# OhBaby10-1.net
KiCad netlist of a schematic drawn in EAGLE
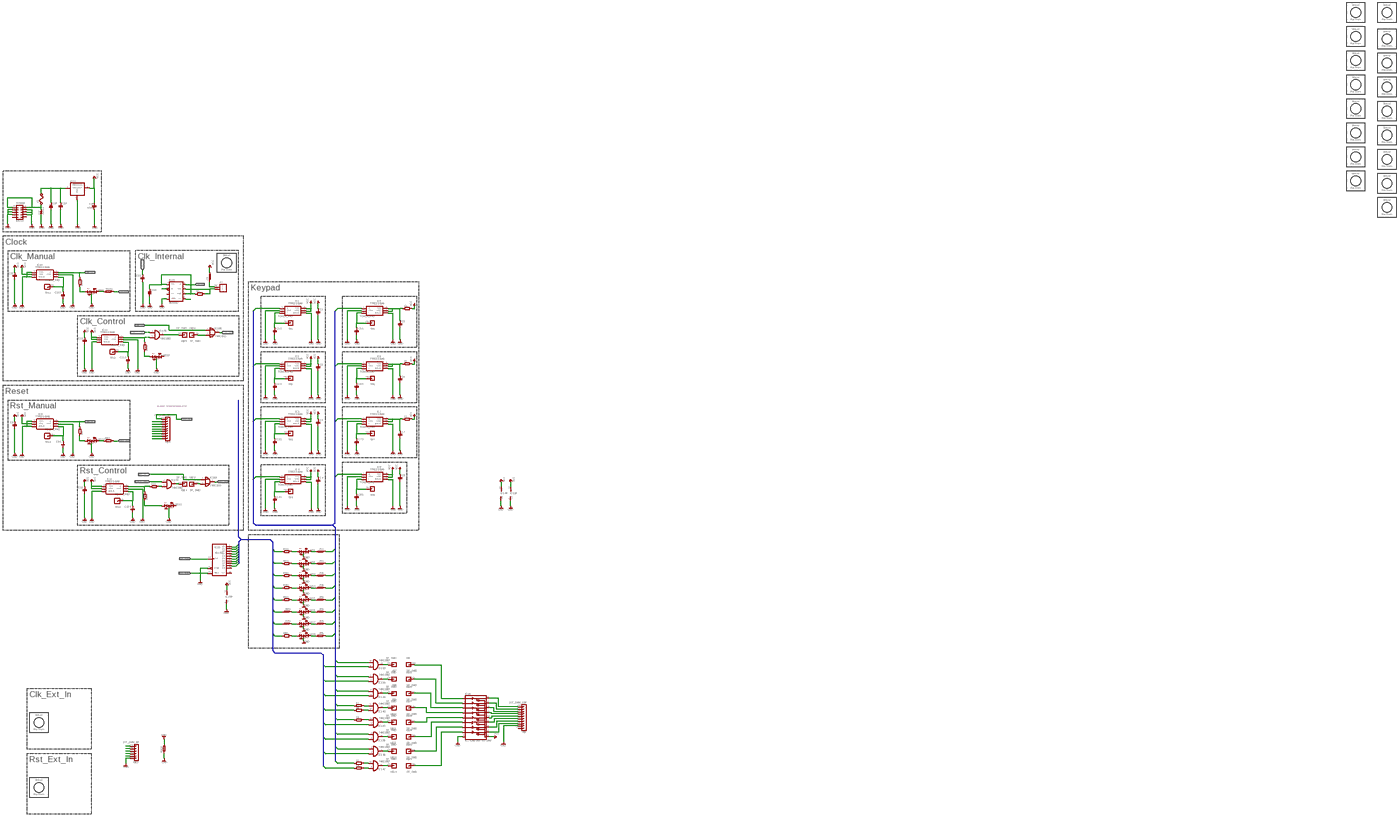
[diagram p0: schematic, sheet 1, overview]
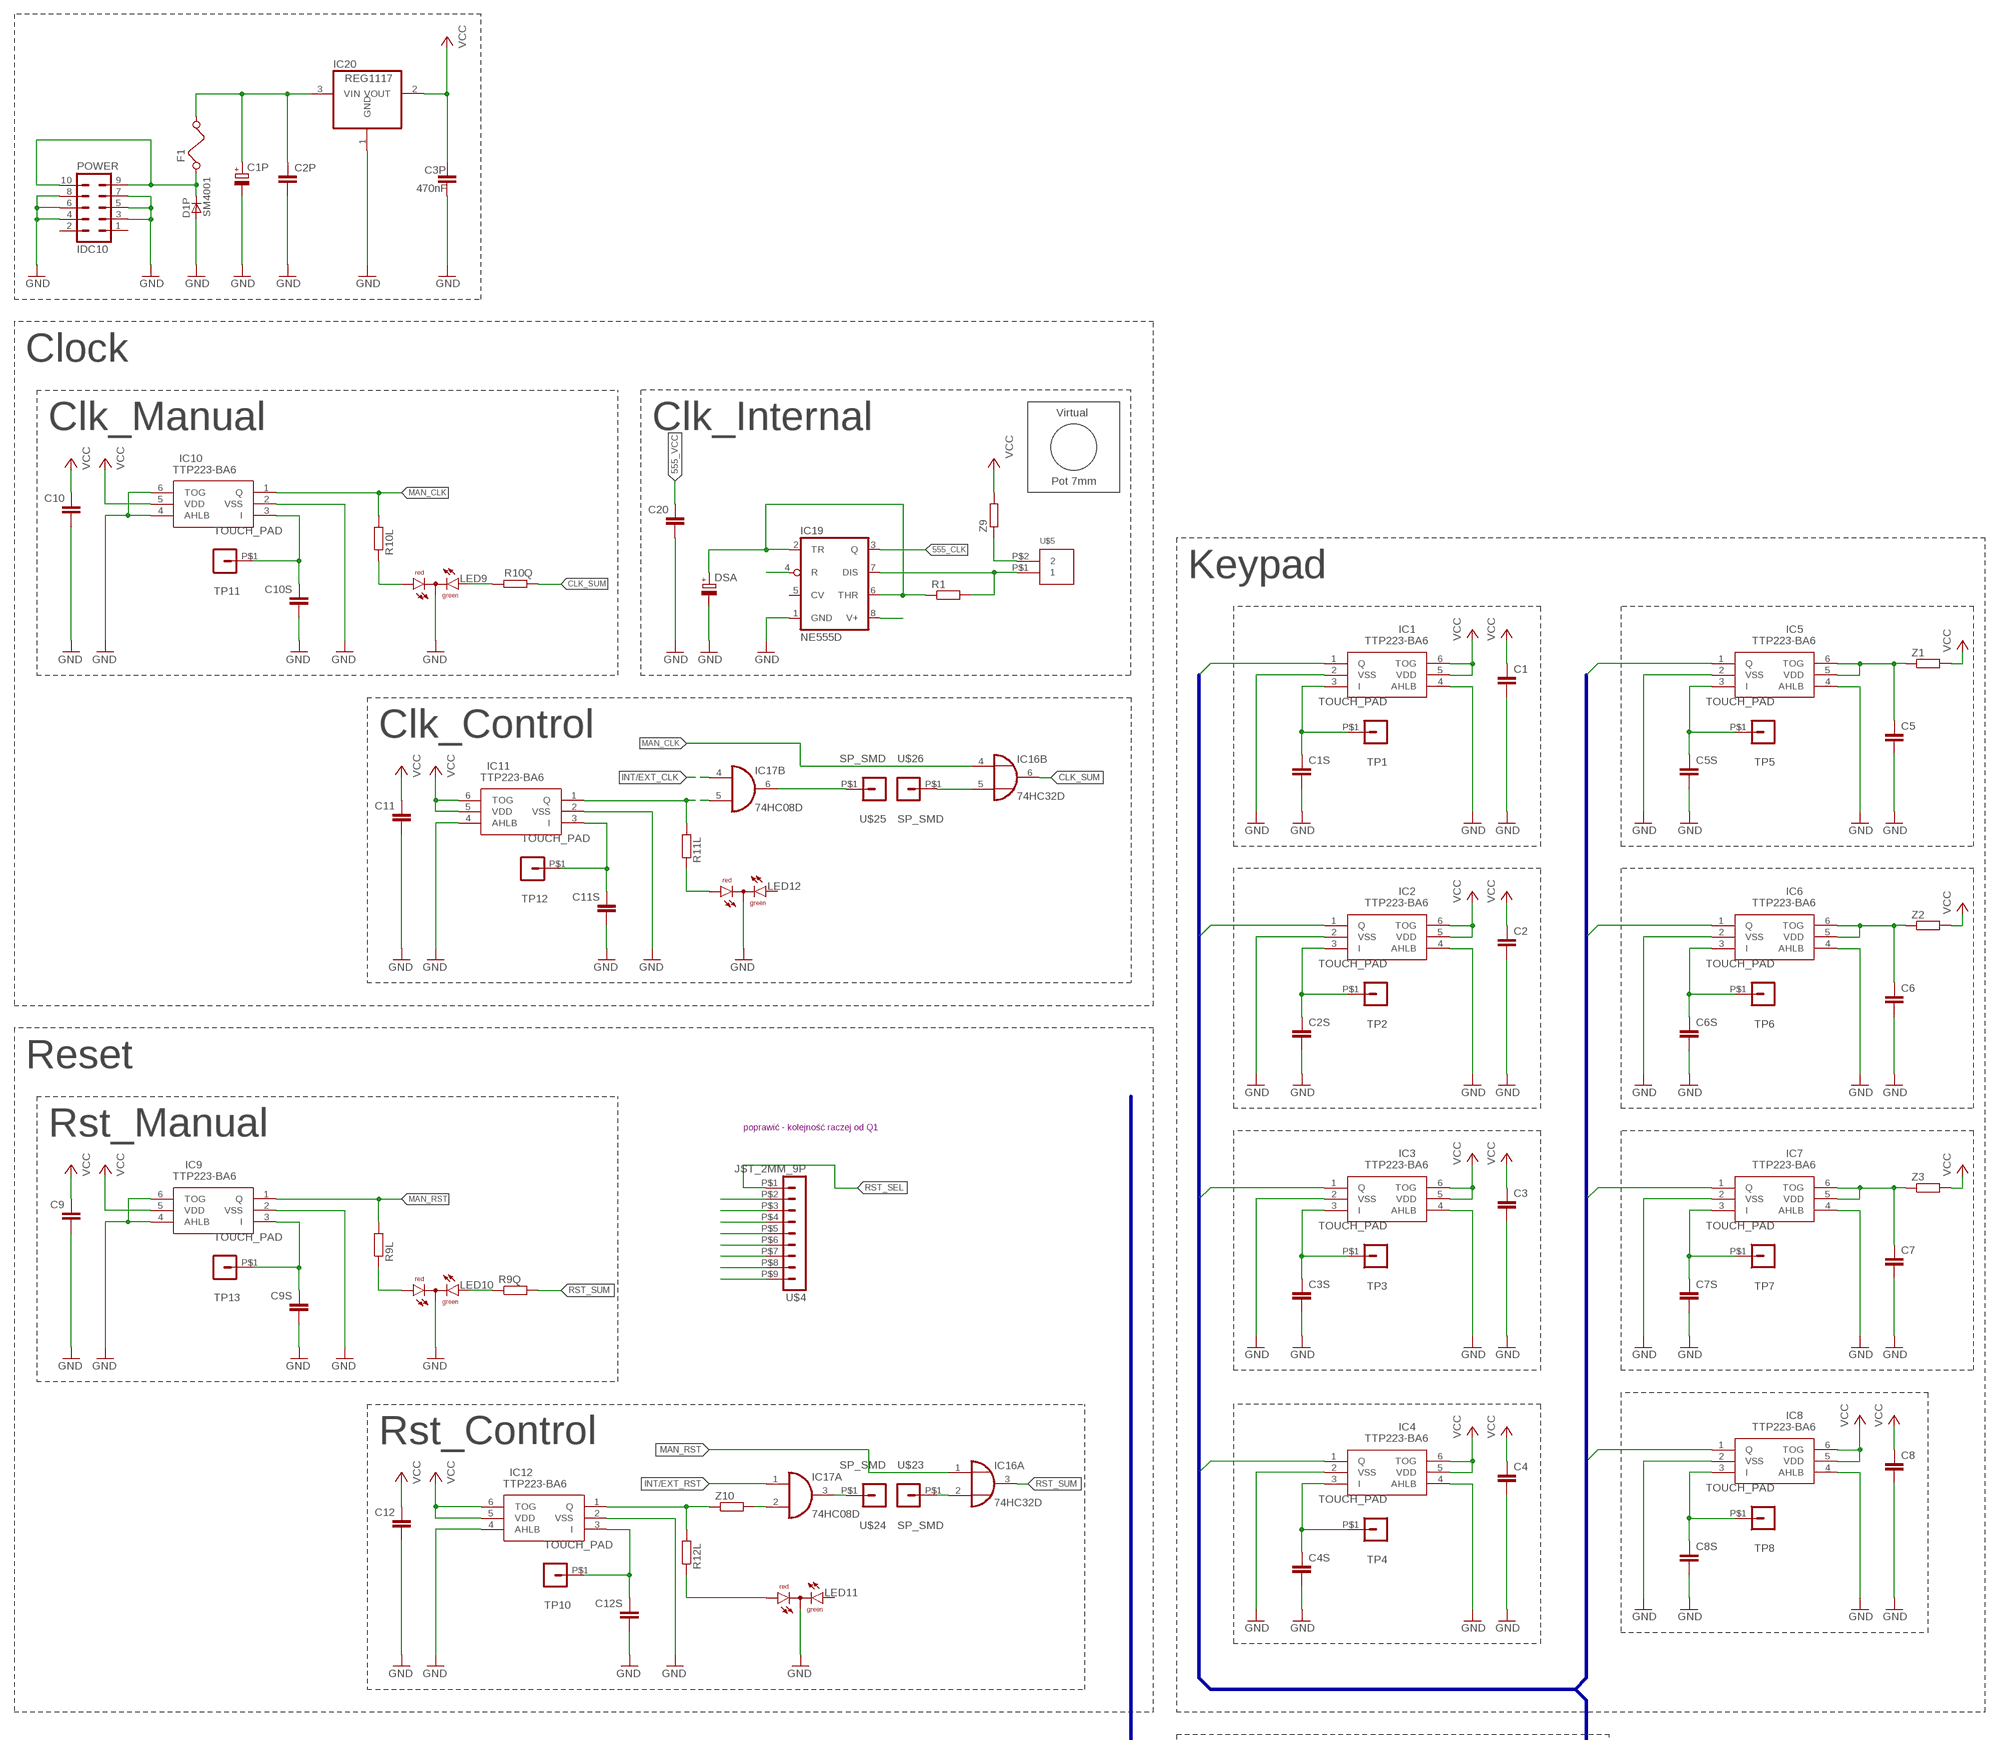
[diagram p1: schematic, sheet 1, part 1 of 5]
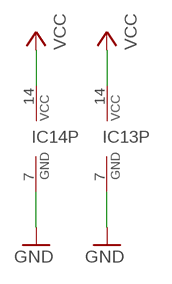
[diagram p2: schematic, sheet 1, part 2 of 5]
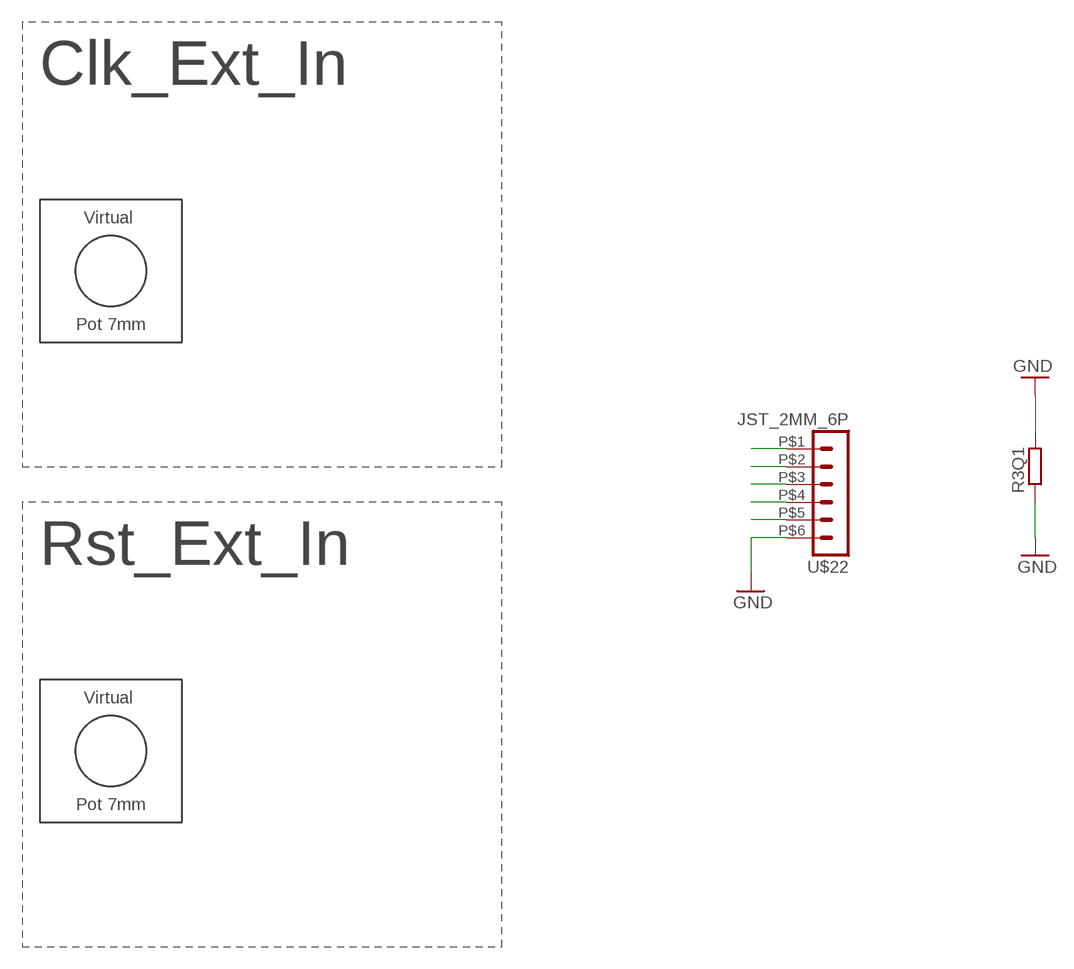
[diagram p3: schematic, sheet 1, part 3 of 5]
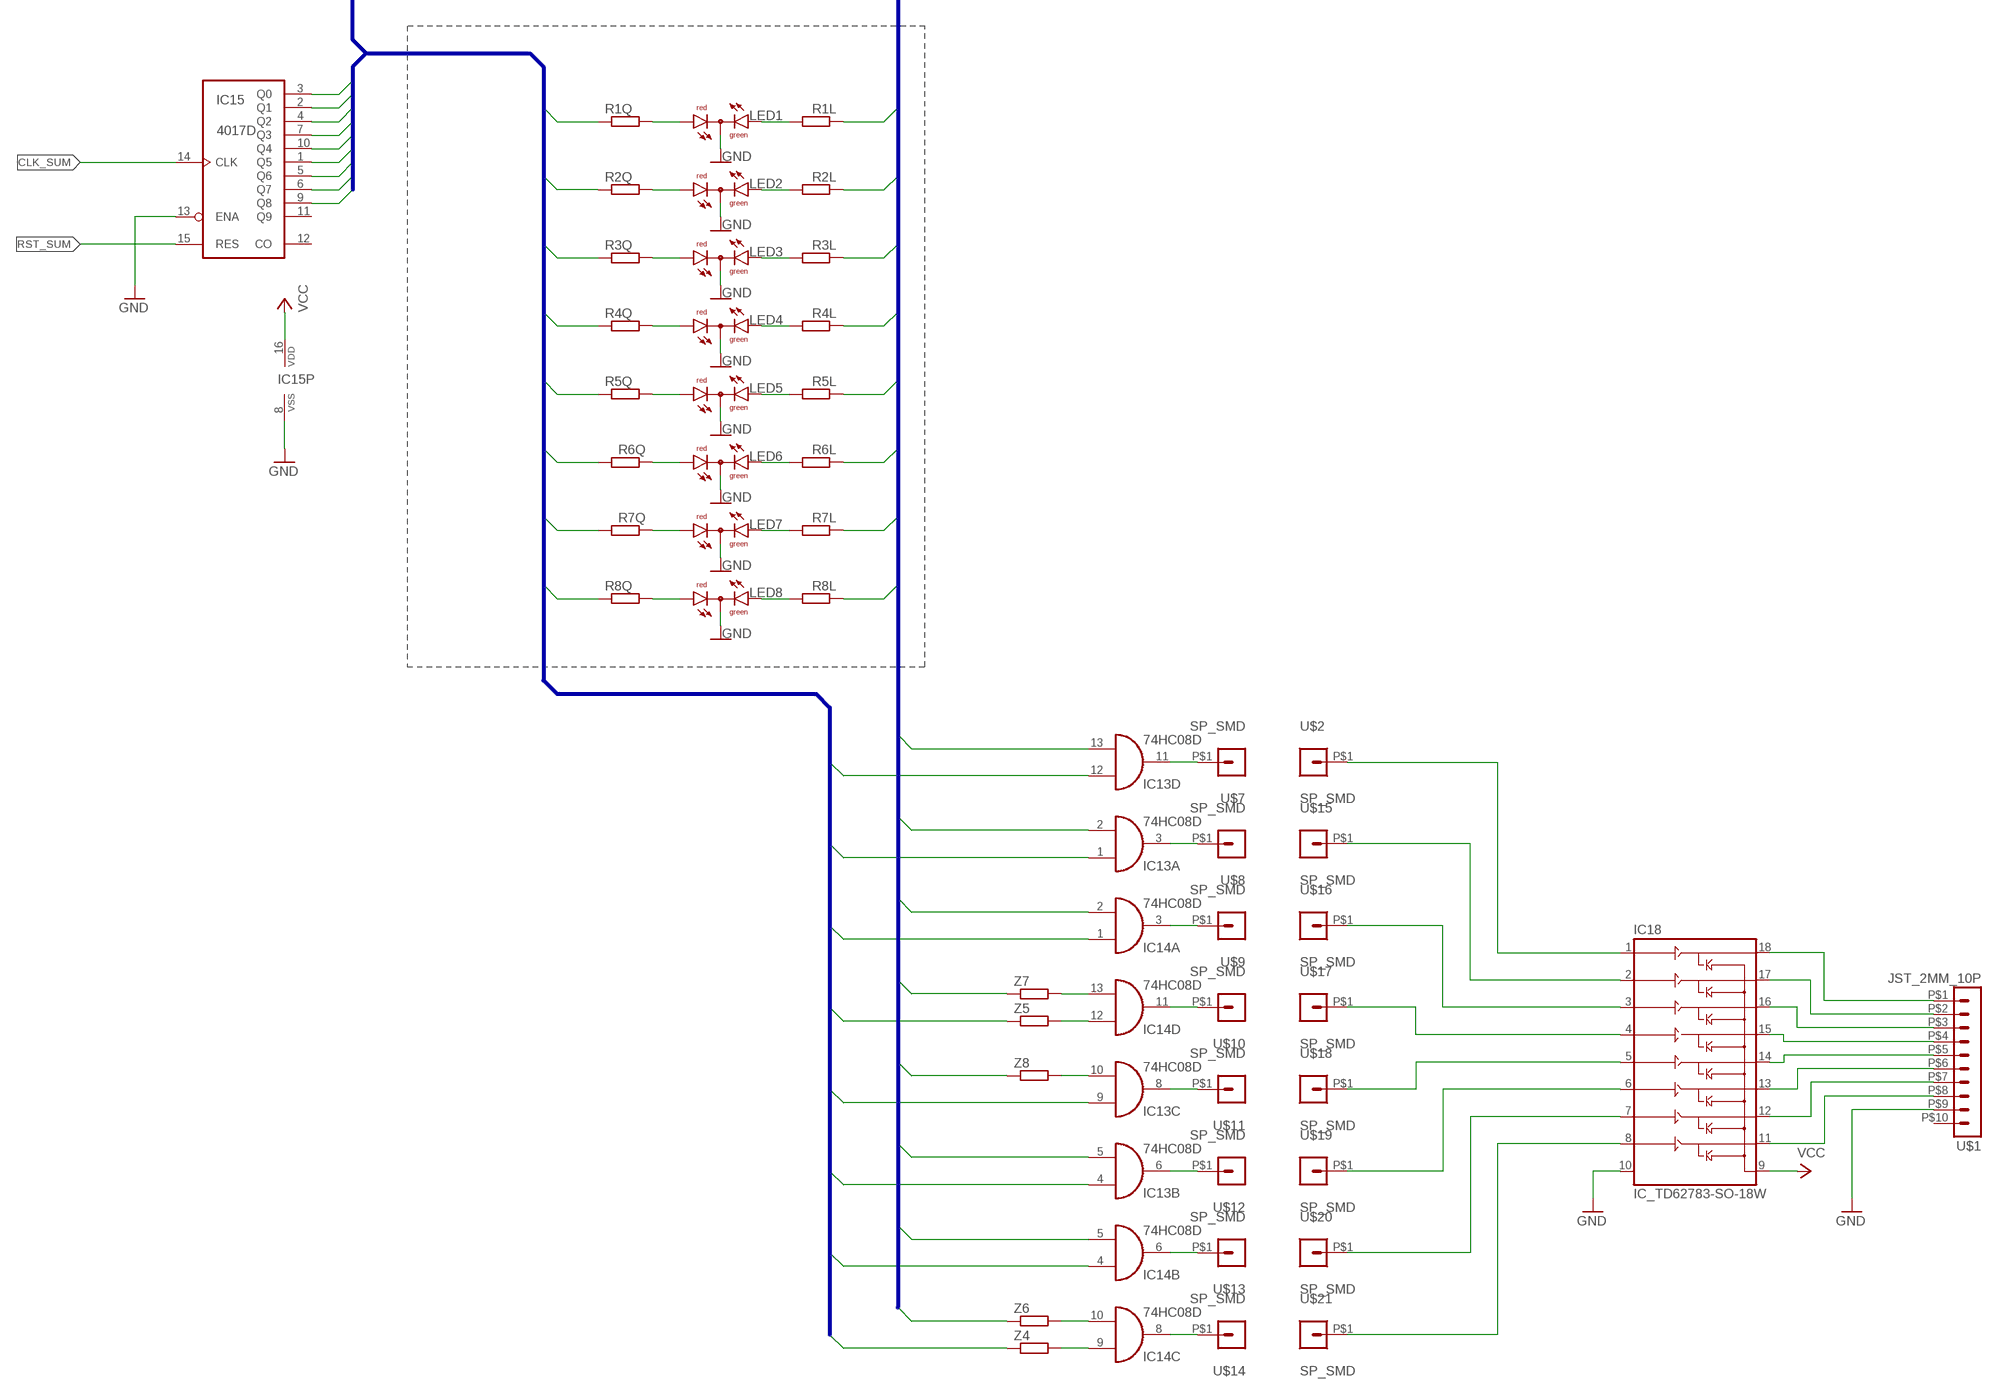
[diagram p4: schematic, sheet 1, part 4 of 5]
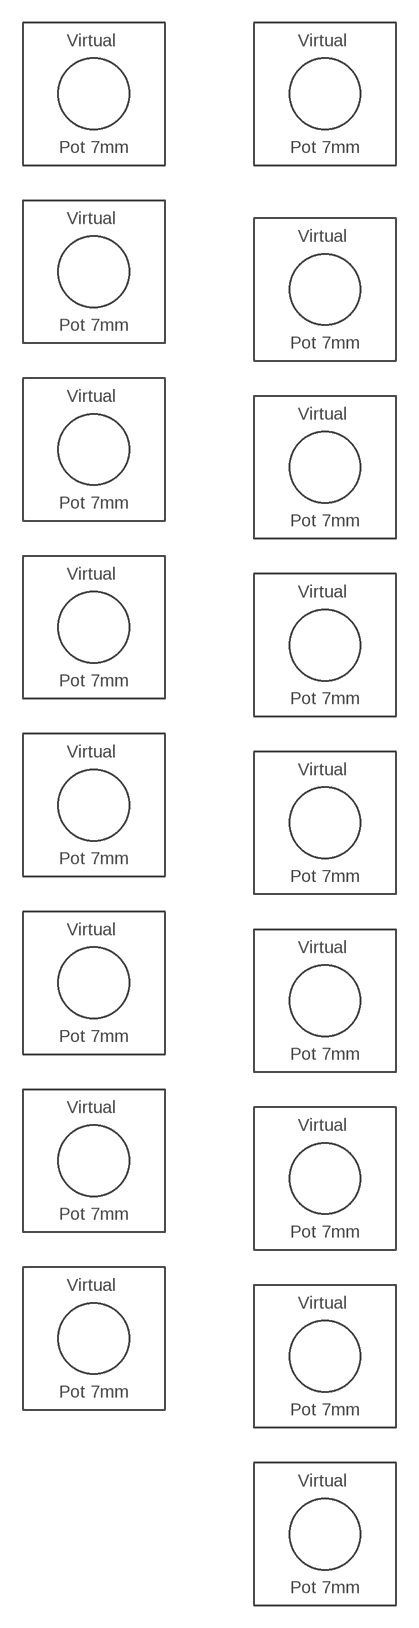
[diagram p5: schematic, sheet 1, part 5 of 5]

(export (version "E")
  (design (tool "Eeschema 10.0.6"))
  (components
    (comp (ref "C1")
      (value "C-EUC0805")
      (footprint "eagle-import:C0805")
      (libsource (lib "eagle-import") (part "rcl_334_C-EUC0805"))
    )
    (comp (ref "C1P")
      (value "CPOL-EU153CLV-0405")
      (footprint "eagle-import:153CLV-0405")
      (libsource (lib "eagle-import") (part "CPOL-EU153CLV-0405"))
    )
    (comp (ref "C1S")
      (value "C-EUC0805")
      (footprint "eagle-import:C0805")
      (libsource (lib "eagle-import") (part "rcl_334_C-EUC0805"))
    )
    (comp (ref "C2")
      (value "C-EUC0805")
      (footprint "eagle-import:C0805")
      (libsource (lib "eagle-import") (part "rcl_334_C-EUC0805"))
    )
    (comp (ref "C2P")
      (value "C-EUC0805K")
      (footprint "eagle-import:C0805K")
      (libsource (lib "eagle-import") (part "rcl_334_C-EUC0805K"))
    )
    (comp (ref "C2S")
      (value "C-EUC0805")
      (footprint "eagle-import:C0805")
      (libsource (lib "eagle-import") (part "rcl_334_C-EUC0805"))
    )
    (comp (ref "C3")
      (value "C-EUC0805")
      (footprint "eagle-import:C0805")
      (libsource (lib "eagle-import") (part "rcl_334_C-EUC0805"))
    )
    (comp (ref "C3P")
      (value "470nF")
      (footprint "eagle-import:C0805")
      (fields (field (name "SPICEPREFIX") "C"))
      (libsource (lib "eagle-import") (part "C-EUC0805"))
    )
    (comp (ref "C3S")
      (value "C-EUC0805")
      (footprint "eagle-import:C0805")
      (libsource (lib "eagle-import") (part "rcl_334_C-EUC0805"))
    )
    (comp (ref "C4")
      (value "C-EUC0805")
      (footprint "eagle-import:C0805")
      (libsource (lib "eagle-import") (part "rcl_334_C-EUC0805"))
    )
    (comp (ref "C4S")
      (value "C-EUC0805")
      (footprint "eagle-import:C0805")
      (libsource (lib "eagle-import") (part "rcl_334_C-EUC0805"))
    )
    (comp (ref "C5")
      (value "C-EUC0805")
      (footprint "eagle-import:C0805")
      (libsource (lib "eagle-import") (part "rcl_334_C-EUC0805"))
    )
    (comp (ref "C5S")
      (value "C-EUC0805")
      (footprint "eagle-import:C0805")
      (libsource (lib "eagle-import") (part "rcl_334_C-EUC0805"))
    )
    (comp (ref "C6")
      (value "C-EUC0805")
      (footprint "eagle-import:C0805")
      (libsource (lib "eagle-import") (part "rcl_334_C-EUC0805"))
    )
    (comp (ref "C6S")
      (value "C-EUC0805")
      (footprint "eagle-import:C0805")
      (libsource (lib "eagle-import") (part "rcl_334_C-EUC0805"))
    )
    (comp (ref "C7")
      (value "C-EUC0805")
      (footprint "eagle-import:C0805")
      (libsource (lib "eagle-import") (part "rcl_334_C-EUC0805"))
    )
    (comp (ref "C7S")
      (value "C-EUC0805")
      (footprint "eagle-import:C0805")
      (libsource (lib "eagle-import") (part "rcl_334_C-EUC0805"))
    )
    (comp (ref "C8")
      (value "C-EUC0805")
      (footprint "eagle-import:C0805")
      (libsource (lib "eagle-import") (part "rcl_334_C-EUC0805"))
    )
    (comp (ref "C8S")
      (value "C-EUC0805")
      (footprint "eagle-import:C0805")
      (libsource (lib "eagle-import") (part "rcl_334_C-EUC0805"))
    )
    (comp (ref "C9")
      (value "C-EUC0805")
      (footprint "eagle-import:C0805")
      (libsource (lib "eagle-import") (part "rcl_334_C-EUC0805"))
    )
    (comp (ref "C9S")
      (value "C-EUC0805")
      (footprint "eagle-import:C0805")
      (libsource (lib "eagle-import") (part "rcl_334_C-EUC0805"))
    )
    (comp (ref "C10")
      (value "C-EUC0805")
      (footprint "eagle-import:C0805")
      (libsource (lib "eagle-import") (part "rcl_334_C-EUC0805"))
    )
    (comp (ref "C10S")
      (value "C-EUC0805")
      (footprint "eagle-import:C0805")
      (libsource (lib "eagle-import") (part "rcl_334_C-EUC0805"))
    )
    (comp (ref "C11")
      (value "C-EUC0805")
      (footprint "eagle-import:C0805")
      (libsource (lib "eagle-import") (part "rcl_334_C-EUC0805"))
    )
    (comp (ref "C11S")
      (value "C-EUC0805")
      (footprint "eagle-import:C0805")
      (libsource (lib "eagle-import") (part "rcl_334_C-EUC0805"))
    )
    (comp (ref "C12")
      (value "C-EUC0805")
      (footprint "eagle-import:C0805")
      (libsource (lib "eagle-import") (part "rcl_334_C-EUC0805"))
    )
    (comp (ref "C12S")
      (value "C-EUC0805")
      (footprint "eagle-import:C0805")
      (libsource (lib "eagle-import") (part "rcl_334_C-EUC0805"))
    )
    (comp (ref "C20")
      (value "C-EUC0805")
      (footprint "eagle-import:C0805")
      (libsource (lib "eagle-import") (part "rcl_334_C-EUC0805"))
    )
    (comp (ref "CV_OUT")
      (value "JACK3.5")
      (footprint "eagle-import:JACK_FANCY")
      (libsource (lib "eagle-import") (part "JACK3.5"))
    )
    (comp (ref "D1P")
      (value "SM4001")
      (footprint "eagle-import:MELF-MLL41_DO213AB")
      (libsource (lib "eagle-import") (part "SM4001"))
    )
    (comp (ref "DSA")
      (value "CPOL-EU153CLV-0405")
      (footprint "eagle-import:153CLV-0405")
      (libsource (lib "eagle-import") (part "CPOL-EU153CLV-0405"))
    )
    (comp (ref "EXT_CLK_IN")
      (value "JACK3.5")
      (footprint "eagle-import:JACK_FANCY")
      (libsource (lib "eagle-import") (part "JACK3.5"))
    )
    (comp (ref "EXT_CLK_IN1")
      (value "JACK3.5")
      (footprint "eagle-import:JACK_FANCY")
      (libsource (lib "eagle-import") (part "JACK3.5"))
    )
    (comp (ref "F1")
      (value "FUSEB")
      (footprint "eagle-import:0805")
      (libsource (lib "eagle-import") (part "FUSEB"))
    )
    (comp (ref "IC1")
      (value "TTP223-BA6")
      (footprint "eagle-import:SOT95P285X126-6N")
      (libsource (lib "eagle-import") (part "TTP223-BA6"))
    )
    (comp (ref "IC2")
      (value "TTP223-BA6")
      (footprint "eagle-import:SOT95P285X126-6N")
      (libsource (lib "eagle-import") (part "TTP223-BA6"))
    )
    (comp (ref "IC3")
      (value "TTP223-BA6")
      (footprint "eagle-import:SOT95P285X126-6N")
      (libsource (lib "eagle-import") (part "TTP223-BA6"))
    )
    (comp (ref "IC4")
      (value "TTP223-BA6")
      (footprint "eagle-import:SOT95P285X126-6N")
      (libsource (lib "eagle-import") (part "TTP223-BA6"))
    )
    (comp (ref "IC5")
      (value "TTP223-BA6")
      (footprint "eagle-import:SOT95P285X126-6N")
      (libsource (lib "eagle-import") (part "TTP223-BA6"))
    )
    (comp (ref "IC6")
      (value "TTP223-BA6")
      (footprint "eagle-import:SOT95P285X126-6N")
      (libsource (lib "eagle-import") (part "TTP223-BA6"))
    )
    (comp (ref "IC7")
      (value "TTP223-BA6")
      (footprint "eagle-import:SOT95P285X126-6N")
      (libsource (lib "eagle-import") (part "TTP223-BA6"))
    )
    (comp (ref "IC8")
      (value "TTP223-BA6")
      (footprint "eagle-import:SOT95P285X126-6N")
      (libsource (lib "eagle-import") (part "TTP223-BA6"))
    )
    (comp (ref "IC9")
      (value "TTP223-BA6")
      (footprint "eagle-import:SOT95P285X126-6N")
      (libsource (lib "eagle-import") (part "TTP223-BA6"))
    )
    (comp (ref "IC10")
      (value "TTP223-BA6")
      (footprint "eagle-import:SOT95P285X126-6N")
      (libsource (lib "eagle-import") (part "TTP223-BA6"))
    )
    (comp (ref "IC11")
      (value "TTP223-BA6")
      (footprint "eagle-import:SOT95P285X126-6N")
      (libsource (lib "eagle-import") (part "TTP223-BA6"))
    )
    (comp (ref "IC12")
      (value "TTP223-BA6")
      (footprint "eagle-import:SOT95P285X126-6N")
      (libsource (lib "eagle-import") (part "TTP223-BA6"))
    )
    (comp (ref "IC13")
      (value "74HC08D")
      (footprint "eagle-import:SO14")
      (libsource (lib "eagle-import") (part "7408DHC"))
    )
    (comp (ref "IC14")
      (value "74HC08D")
      (footprint "eagle-import:SO14")
      (libsource (lib "eagle-import") (part "7408DHC"))
    )
    (comp (ref "IC15")
      (value "4017D")
      (footprint "eagle-import:SO16")
      (libsource (lib "eagle-import") (part "4017D"))
    )
    (comp (ref "IC16")
      (value "74HC32D")
      (footprint "eagle-import:SO14")
      (libsource (lib "eagle-import") (part "7432DHC"))
    )
    (comp (ref "IC17")
      (value "74HC08D")
      (footprint "eagle-import:SO14")
      (libsource (lib "eagle-import") (part "7408DHC"))
    )
    (comp (ref "IC18")
      (value "IC_TD62783-SO-18W")
      (footprint "eagle-import:SO-18L")
      (libsource (lib "eagle-import") (part "IC_TD62783-SO-18W"))
    )
    (comp (ref "IC19")
      (value "NE555D")
      (footprint "eagle-import:SO08")
      (libsource (lib "eagle-import") (part "555DNE"))
    )
    (comp (ref "IC20")
      (value "REG1117")
      (footprint "eagle-import:SOT223")
      (libsource (lib "eagle-import") (part "REG1117"))
    )
    (comp (ref "LED1")
      (value "LED_3PIN")
      (footprint "eagle-import:LED_3PIN_SMD")
      (libsource (lib "eagle-import") (part "LED_3PIN"))
    )
    (comp (ref "LED2")
      (value "LED_3PIN")
      (footprint "eagle-import:LED_3PIN_SMD")
      (libsource (lib "eagle-import") (part "LED_3PIN"))
    )
    (comp (ref "LED3")
      (value "LED_3PIN")
      (footprint "eagle-import:LED_3PIN_SMD")
      (libsource (lib "eagle-import") (part "LED_3PIN"))
    )
    (comp (ref "LED4")
      (value "LED_3PIN")
      (footprint "eagle-import:LED_3PIN_SMD")
      (libsource (lib "eagle-import") (part "LED_3PIN"))
    )
    (comp (ref "LED5")
      (value "LED_3PIN")
      (footprint "eagle-import:LED_3PIN_SMD")
      (libsource (lib "eagle-import") (part "LED_3PIN"))
    )
    (comp (ref "LED6")
      (value "LED_3PIN")
      (footprint "eagle-import:LED_3PIN_SMD")
      (libsource (lib "eagle-import") (part "LED_3PIN"))
    )
    (comp (ref "LED7")
      (value "LED_3PIN")
      (footprint "eagle-import:LED_3PIN_SMD")
      (libsource (lib "eagle-import") (part "LED_3PIN"))
    )
    (comp (ref "LED8")
      (value "LED_3PIN")
      (footprint "eagle-import:LED_3PIN_SMD")
      (libsource (lib "eagle-import") (part "LED_3PIN"))
    )
    (comp (ref "LED9")
      (value "LED_3PIN")
      (footprint "eagle-import:LED_3PIN_SMD")
      (libsource (lib "eagle-import") (part "LED_3PIN"))
    )
    (comp (ref "LED10")
      (value "LED_3PIN")
      (footprint "eagle-import:LED_3PIN_SMD")
      (libsource (lib "eagle-import") (part "LED_3PIN"))
    )
    (comp (ref "LED11")
      (value "LED_3PIN")
      (footprint "eagle-import:LED_3PIN_SMD")
      (libsource (lib "eagle-import") (part "LED_3PIN"))
    )
    (comp (ref "LED12")
      (value "LED_3PIN")
      (footprint "eagle-import:LED_3PIN_SMD")
      (libsource (lib "eagle-import") (part "LED_3PIN"))
    )
    (comp (ref "OUT_S1")
      (value "JACK3.5")
      (footprint "eagle-import:JACK_FANCY")
      (libsource (lib "eagle-import") (part "JACK3.5"))
    )
    (comp (ref "OUT_S2")
      (value "JACK3.5")
      (footprint "eagle-import:JACK_FANCY")
      (libsource (lib "eagle-import") (part "JACK3.5"))
    )
    (comp (ref "OUT_S3")
      (value "JACK3.5")
      (footprint "eagle-import:JACK_FANCY")
      (libsource (lib "eagle-import") (part "JACK3.5"))
    )
    (comp (ref "OUT_S4")
      (value "JACK3.5")
      (footprint "eagle-import:JACK_FANCY")
      (libsource (lib "eagle-import") (part "JACK3.5"))
    )
    (comp (ref "OUT_S5")
      (value "JACK3.5")
      (footprint "eagle-import:JACK_FANCY")
      (libsource (lib "eagle-import") (part "JACK3.5"))
    )
    (comp (ref "OUT_S6")
      (value "JACK3.5")
      (footprint "eagle-import:JACK_FANCY")
      (libsource (lib "eagle-import") (part "JACK3.5"))
    )
    (comp (ref "OUT_S7")
      (value "JACK3.5")
      (footprint "eagle-import:JACK_FANCY")
      (libsource (lib "eagle-import") (part "JACK3.5"))
    )
    (comp (ref "OUT_S8")
      (value "JACK3.5")
      (footprint "eagle-import:JACK_FANCY")
      (libsource (lib "eagle-import") (part "JACK3.5"))
    )
    (comp (ref "POT_S1")
      (value "V_POT")
      (footprint "eagle-import:POT_FANCY")
      (libsource (lib "eagle-import") (part "V_POT"))
    )
    (comp (ref "POT_S2")
      (value "V_POT")
      (footprint "eagle-import:POT_FANCY")
      (libsource (lib "eagle-import") (part "V_POT"))
    )
    (comp (ref "POT_S3")
      (value "V_POT")
      (footprint "eagle-import:POT_FANCY")
      (libsource (lib "eagle-import") (part "V_POT"))
    )
    (comp (ref "POT_S4")
      (value "V_POT")
      (footprint "eagle-import:POT_FANCY")
      (libsource (lib "eagle-import") (part "V_POT"))
    )
    (comp (ref "POT_S5")
      (value "V_POT")
      (footprint "eagle-import:POT_FANCY")
      (libsource (lib "eagle-import") (part "V_POT"))
    )
    (comp (ref "POT_S6")
      (value "V_POT")
      (footprint "eagle-import:POT_FANCY")
      (libsource (lib "eagle-import") (part "V_POT"))
    )
    (comp (ref "POT_S7")
      (value "V_POT")
      (footprint "eagle-import:POT_FANCY")
      (libsource (lib "eagle-import") (part "V_POT"))
    )
    (comp (ref "POT_S8")
      (value "V_POT")
      (footprint "eagle-import:POT_FANCY")
      (libsource (lib "eagle-import") (part "V_POT"))
    )
    (comp (ref "POWER")
      (value "IDC10")
      (footprint "eagle-import:ML10")
      (libsource (lib "eagle-import") (part "IDC10"))
    )
    (comp (ref "R1")
      (value "R-EU_R1206")
      (footprint "eagle-import:R1206")
      (libsource (lib "eagle-import") (part "R-EU_R1206"))
    )
    (comp (ref "R1L")
      (value "R-EU_R0805")
      (footprint "eagle-import:R0805")
      (libsource (lib "eagle-import") (part "R-EU_R0805"))
    )
    (comp (ref "R1Q")
      (value "R-EU_R1206")
      (footprint "eagle-import:R1206")
      (libsource (lib "eagle-import") (part "R-EU_R1206"))
    )
    (comp (ref "R2L")
      (value "R-EU_R0805")
      (footprint "eagle-import:R0805")
      (libsource (lib "eagle-import") (part "R-EU_R0805"))
    )
    (comp (ref "R2Q")
      (value "R-EU_R1206")
      (footprint "eagle-import:R1206")
      (libsource (lib "eagle-import") (part "R-EU_R1206"))
    )
    (comp (ref "R3L")
      (value "R-EU_R0805")
      (footprint "eagle-import:R0805")
      (libsource (lib "eagle-import") (part "R-EU_R0805"))
    )
    (comp (ref "R3Q")
      (value "R-EU_R1206")
      (footprint "eagle-import:R1206")
      (libsource (lib "eagle-import") (part "R-EU_R1206"))
    )
    (comp (ref "R3Q1")
      (value "R-EU_R1206")
      (footprint "eagle-import:R1206")
      (libsource (lib "eagle-import") (part "R-EU_R1206"))
    )
    (comp (ref "R4L")
      (value "R-EU_R0805")
      (footprint "eagle-import:R0805")
      (libsource (lib "eagle-import") (part "R-EU_R0805"))
    )
    (comp (ref "R4Q")
      (value "R-EU_R1206")
      (footprint "eagle-import:R1206")
      (libsource (lib "eagle-import") (part "R-EU_R1206"))
    )
    (comp (ref "R5L")
      (value "R-EU_R0805")
      (footprint "eagle-import:R0805")
      (libsource (lib "eagle-import") (part "R-EU_R0805"))
    )
    (comp (ref "R5Q")
      (value "R-EU_R1206")
      (footprint "eagle-import:R1206")
      (libsource (lib "eagle-import") (part "R-EU_R1206"))
    )
    (comp (ref "R6L")
      (value "R-EU_R0805")
      (footprint "eagle-import:R0805")
      (libsource (lib "eagle-import") (part "R-EU_R0805"))
    )
    (comp (ref "R6Q")
      (value "R-EU_R0805")
      (footprint "eagle-import:R0805")
      (libsource (lib "eagle-import") (part "R-EU_R0805"))
    )
    (comp (ref "R7L")
      (value "R-EU_R0805")
      (footprint "eagle-import:R0805")
      (libsource (lib "eagle-import") (part "R-EU_R0805"))
    )
    (comp (ref "R7Q")
      (value "R-EU_R0805")
      (footprint "eagle-import:R0805")
      (libsource (lib "eagle-import") (part "R-EU_R0805"))
    )
    (comp (ref "R8L")
      (value "R-EU_R0805")
      (footprint "eagle-import:R0805")
      (libsource (lib "eagle-import") (part "R-EU_R0805"))
    )
    (comp (ref "R8Q")
      (value "R-EU_R1206")
      (footprint "eagle-import:R1206")
      (libsource (lib "eagle-import") (part "R-EU_R1206"))
    )
    (comp (ref "R9L")
      (value "R-EU_R0805")
      (footprint "eagle-import:R0805")
      (libsource (lib "eagle-import") (part "R-EU_R0805"))
    )
    (comp (ref "R9Q")
      (value "R-EU_R1206")
      (footprint "eagle-import:R1206")
      (libsource (lib "eagle-import") (part "R-EU_R1206"))
    )
    (comp (ref "R10L")
      (value "R-EU_R0805")
      (footprint "eagle-import:R0805")
      (libsource (lib "eagle-import") (part "R-EU_R0805"))
    )
    (comp (ref "R10Q")
      (value "R-EU_R0805")
      (footprint "eagle-import:R0805")
      (libsource (lib "eagle-import") (part "R-EU_R0805"))
    )
    (comp (ref "R11L")
      (value "R-EU_R0805")
      (footprint "eagle-import:R0805")
      (libsource (lib "eagle-import") (part "R-EU_R0805"))
    )
    (comp (ref "R12L")
      (value "R-EU_R0805")
      (footprint "eagle-import:R0805")
      (libsource (lib "eagle-import") (part "R-EU_R0805"))
    )
    (comp (ref "TP1")
      (value "TOUCH_PAD")
      (footprint "eagle-import:TOUCH_PAD_8X8")
      (libsource (lib "eagle-import") (part "TOUCH_PAD"))
    )
    (comp (ref "TP2")
      (value "TOUCH_PAD")
      (footprint "eagle-import:TOUCH_PAD_8X8")
      (libsource (lib "eagle-import") (part "TOUCH_PAD"))
    )
    (comp (ref "TP3")
      (value "TOUCH_PAD")
      (footprint "eagle-import:TOUCH_PAD_8X8")
      (libsource (lib "eagle-import") (part "TOUCH_PAD"))
    )
    (comp (ref "TP4")
      (value "TOUCH_PAD")
      (footprint "eagle-import:TOUCH_PAD_8X8")
      (libsource (lib "eagle-import") (part "TOUCH_PAD"))
    )
    (comp (ref "TP5")
      (value "TOUCH_PAD")
      (footprint "eagle-import:TOUCH_PAD_8X8")
      (libsource (lib "eagle-import") (part "TOUCH_PAD"))
    )
    (comp (ref "TP6")
      (value "TOUCH_PAD")
      (footprint "eagle-import:TOUCH_PAD_8X8")
      (libsource (lib "eagle-import") (part "TOUCH_PAD"))
    )
    (comp (ref "TP7")
      (value "TOUCH_PAD")
      (footprint "eagle-import:TOUCH_PAD_8X8")
      (libsource (lib "eagle-import") (part "TOUCH_PAD"))
    )
    (comp (ref "TP8")
      (value "TOUCH_PAD")
      (footprint "eagle-import:TOUCH_PAD_8X8")
      (libsource (lib "eagle-import") (part "TOUCH_PAD"))
    )
    (comp (ref "TP10")
      (value "TOUCH_PAD")
      (footprint "eagle-import:TOUCH_PAD_8X8")
      (libsource (lib "eagle-import") (part "TOUCH_PAD"))
    )
    (comp (ref "TP11")
      (value "TOUCH_PAD")
      (footprint "eagle-import:TOUCH_PAD_8X8")
      (libsource (lib "eagle-import") (part "TOUCH_PAD"))
    )
    (comp (ref "TP12")
      (value "TOUCH_PAD")
      (footprint "eagle-import:TOUCH_PAD_8X8")
      (libsource (lib "eagle-import") (part "TOUCH_PAD"))
    )
    (comp (ref "TP13")
      (value "TOUCH_PAD")
      (footprint "eagle-import:TOUCH_PAD_8X8")
      (libsource (lib "eagle-import") (part "TOUCH_PAD"))
    )
    (comp (ref "U$1")
      (value "JST_2MM_10P")
      (footprint "eagle-import:JST_2MM_10P")
      (libsource (lib "eagle-import") (part "JST_2MM_10P"))
    )
    (comp (ref "U$2")
      (value "SP_SMD")
      (footprint "eagle-import:SINGLE_PAD_SMD")
      (libsource (lib "eagle-import") (part "SP_SMD"))
    )
    (comp (ref "U$4")
      (value "JST_2MM_9P")
      (footprint "eagle-import:JST_2MM_9P")
      (libsource (lib "eagle-import") (part "JST_2MM_9P"))
    )
    (comp (ref "U$5")
      (value "JST_2MM_2P")
      (footprint "eagle-import:JST_2MM_2P")
      (libsource (lib "eagle-import") (part "JST_2MM_2P"))
    )
    (comp (ref "U$6")
      (value "V_POT")
      (footprint "eagle-import:POT_FANCY")
      (libsource (lib "eagle-import") (part "V_POT"))
    )
    (comp (ref "U$7")
      (value "SP_SMD")
      (footprint "eagle-import:SINGLE_PAD_SMD")
      (libsource (lib "eagle-import") (part "SP_SMD"))
    )
    (comp (ref "U$8")
      (value "SP_SMD")
      (footprint "eagle-import:SINGLE_PAD_SMD")
      (libsource (lib "eagle-import") (part "SP_SMD"))
    )
    (comp (ref "U$9")
      (value "SP_SMD")
      (footprint "eagle-import:SINGLE_PAD_SMD")
      (libsource (lib "eagle-import") (part "SP_SMD"))
    )
    (comp (ref "U$10")
      (value "SP_SMD")
      (footprint "eagle-import:SINGLE_PAD_SMD")
      (libsource (lib "eagle-import") (part "SP_SMD"))
    )
    (comp (ref "U$11")
      (value "SP_SMD")
      (footprint "eagle-import:SINGLE_PAD_SMD")
      (libsource (lib "eagle-import") (part "SP_SMD"))
    )
    (comp (ref "U$12")
      (value "SP_SMD")
      (footprint "eagle-import:SINGLE_PAD_SMD")
      (libsource (lib "eagle-import") (part "SP_SMD"))
    )
    (comp (ref "U$13")
      (value "SP_SMD")
      (footprint "eagle-import:SINGLE_PAD_SMD")
      (libsource (lib "eagle-import") (part "SP_SMD"))
    )
    (comp (ref "U$14")
      (value "SP_SMD")
      (footprint "eagle-import:SINGLE_PAD_SMD")
      (libsource (lib "eagle-import") (part "SP_SMD"))
    )
    (comp (ref "U$15")
      (value "SP_SMD")
      (footprint "eagle-import:SINGLE_PAD_SMD")
      (libsource (lib "eagle-import") (part "SP_SMD"))
    )
    (comp (ref "U$16")
      (value "SP_SMD")
      (footprint "eagle-import:SINGLE_PAD_SMD")
      (libsource (lib "eagle-import") (part "SP_SMD"))
    )
    (comp (ref "U$17")
      (value "SP_SMD")
      (footprint "eagle-import:SINGLE_PAD_SMD")
      (libsource (lib "eagle-import") (part "SP_SMD"))
    )
    (comp (ref "U$18")
      (value "SP_SMD")
      (footprint "eagle-import:SINGLE_PAD_SMD")
      (libsource (lib "eagle-import") (part "SP_SMD"))
    )
    (comp (ref "U$19")
      (value "SP_SMD")
      (footprint "eagle-import:SINGLE_PAD_SMD")
      (libsource (lib "eagle-import") (part "SP_SMD"))
    )
    (comp (ref "U$20")
      (value "SP_SMD")
      (footprint "eagle-import:SINGLE_PAD_SMD")
      (libsource (lib "eagle-import") (part "SP_SMD"))
    )
    (comp (ref "U$21")
      (value "SP_SMD")
      (footprint "eagle-import:SINGLE_PAD_SMD")
      (libsource (lib "eagle-import") (part "SP_SMD"))
    )
    (comp (ref "U$22")
      (value "JST_2MM_6P")
      (footprint "eagle-import:JST_2MM_6P")
      (libsource (lib "eagle-import") (part "JST_2MM_6P"))
    )
    (comp (ref "U$23")
      (value "SP_SMD")
      (footprint "eagle-import:SINGLE_PAD_SMD")
      (libsource (lib "eagle-import") (part "SP_SMD"))
    )
    (comp (ref "U$24")
      (value "SP_SMD")
      (footprint "eagle-import:SINGLE_PAD_SMD")
      (libsource (lib "eagle-import") (part "SP_SMD"))
    )
    (comp (ref "U$25")
      (value "SP_SMD")
      (footprint "eagle-import:SINGLE_PAD_SMD")
      (libsource (lib "eagle-import") (part "SP_SMD"))
    )
    (comp (ref "U$26")
      (value "SP_SMD")
      (footprint "eagle-import:SINGLE_PAD_SMD")
      (libsource (lib "eagle-import") (part "SP_SMD"))
    )
    (comp (ref "Z1")
      (value "R-EU_R1206")
      (footprint "eagle-import:R1206")
      (libsource (lib "eagle-import") (part "R-EU_R1206"))
    )
    (comp (ref "Z2")
      (value "R-EU_R1206")
      (footprint "eagle-import:R1206")
      (libsource (lib "eagle-import") (part "R-EU_R1206"))
    )
    (comp (ref "Z3")
      (value "R-EU_R2010")
      (footprint "eagle-import:R2010")
      (libsource (lib "eagle-import") (part "R-EU_R2010"))
    )
    (comp (ref "Z4")
      (value "R-EU_R2010")
      (footprint "eagle-import:R2010")
      (libsource (lib "eagle-import") (part "R-EU_R2010"))
    )
    (comp (ref "Z5")
      (value "R-EU_R2010")
      (footprint "eagle-import:R2010")
      (libsource (lib "eagle-import") (part "R-EU_R2010"))
    )
    (comp (ref "Z6")
      (value "R-EU_R2010")
      (footprint "eagle-import:R2010")
      (libsource (lib "eagle-import") (part "R-EU_R2010"))
    )
    (comp (ref "Z7")
      (value "R-EU_R2010")
      (footprint "eagle-import:R2010")
      (libsource (lib "eagle-import") (part "R-EU_R2010"))
    )
    (comp (ref "Z8")
      (value "R-EU_R1206")
      (footprint "eagle-import:R1206")
      (libsource (lib "eagle-import") (part "R-EU_R1206"))
    )
    (comp (ref "Z9")
      (value "R-EU_R1206")
      (footprint "eagle-import:R1206")
      (libsource (lib "eagle-import") (part "R-EU_R1206"))
    )
    (comp (ref "Z10")
      (value "R-EU_R2010")
      (footprint "eagle-import:R2010")
      (libsource (lib "eagle-import") (part "R-EU_R2010"))
    )
  )
  (nets
    (net (code "1") (name "/4017_Q0") (class "Default")
      (node (ref "IC13") (pin "12") (pinfunction "I0_12") (pintype "input"))
      (node (ref "IC15") (pin "3") (pinfunction "Q0_3") (pintype "output"))
      (node (ref "R1Q") (pin "1") (pinfunction "1_1") (pintype "passive"))
    )
    (net (code "2") (name "/4017_Q1") (class "Default")
      (node (ref "IC13") (pin "1") (pinfunction "I0_1") (pintype "input"))
      (node (ref "IC15") (pin "2") (pinfunction "Q1_2") (pintype "output"))
      (node (ref "R2Q") (pin "1") (pinfunction "1_1") (pintype "passive"))
      (node (ref "U$4") (pin "P$8") (pinfunction "8_P$8") (pintype "passive"))
    )
    (net (code "3") (name "/4017_Q2") (class "Default")
      (node (ref "IC14") (pin "1") (pinfunction "I0_1") (pintype "input"))
      (node (ref "IC15") (pin "4") (pinfunction "Q2_4") (pintype "output"))
      (node (ref "R3Q") (pin "1") (pinfunction "1_1") (pintype "passive"))
      (node (ref "U$4") (pin "P$7") (pinfunction "7_P$7") (pintype "passive"))
    )
    (net (code "4") (name "/4017_Q3") (class "Default")
      (node (ref "IC15") (pin "7") (pinfunction "Q3_7") (pintype "output"))
      (node (ref "R4Q") (pin "1") (pinfunction "1_1") (pintype "passive"))
      (node (ref "U$4") (pin "P$4") (pinfunction "4_P$4") (pintype "passive"))
      (node (ref "Z5") (pin "1") (pinfunction "1_1") (pintype "passive"))
    )
    (net (code "5") (name "/4017_Q4") (class "Default")
      (node (ref "IC13") (pin "9") (pinfunction "I0_9") (pintype "input"))
      (node (ref "IC15") (pin "10") (pinfunction "Q4_10") (pintype "output"))
      (node (ref "R5Q") (pin "1") (pinfunction "1_1") (pintype "passive"))
      (node (ref "U$4") (pin "P$3") (pinfunction "3_P$3") (pintype "passive"))
    )
    (net (code "6") (name "/4017_Q5") (class "Default")
      (node (ref "IC13") (pin "4") (pinfunction "I0_4") (pintype "input"))
      (node (ref "IC15") (pin "1") (pinfunction "Q5_1") (pintype "output"))
      (node (ref "R6Q") (pin "2") (pinfunction "2_2") (pintype "passive"))
      (node (ref "U$4") (pin "P$9") (pinfunction "9_P$9") (pintype "passive"))
    )
    (net (code "7") (name "/4017_Q6") (class "Default")
      (node (ref "IC14") (pin "4") (pinfunction "I0_4") (pintype "input"))
      (node (ref "IC15") (pin "5") (pinfunction "Q6_5") (pintype "output"))
      (node (ref "R7Q") (pin "2") (pinfunction "2_2") (pintype "passive"))
      (node (ref "U$4") (pin "P$6") (pinfunction "6_P$6") (pintype "passive"))
    )
    (net (code "8") (name "/4017_Q7") (class "Default")
      (node (ref "IC15") (pin "6") (pinfunction "Q7_6") (pintype "output"))
      (node (ref "R8Q") (pin "1") (pinfunction "1_1") (pintype "passive"))
      (node (ref "U$4") (pin "P$5") (pinfunction "5_P$5") (pintype "passive"))
      (node (ref "Z4") (pin "1") (pinfunction "1_1") (pintype "passive"))
    )
    (net (code "9") (name "/4017_Q8") (class "Default")
      (node (ref "IC15") (pin "9") (pinfunction "Q8_9") (pintype "output"))
      (node (ref "U$4") (pin "P$2") (pinfunction "2_P$2") (pintype "passive"))
    )
    (net (code "10") (name "/KEY1") (class "Default")
      (node (ref "IC1") (pin "1") (pinfunction "Q_1") (pintype "bidirectional"))
      (node (ref "IC13") (pin "13") (pinfunction "I1_13") (pintype "input"))
      (node (ref "R1L") (pin "1") (pinfunction "1_1") (pintype "passive"))
    )
    (net (code "11") (name "/KEY2") (class "Default")
      (node (ref "IC13") (pin "2") (pinfunction "I1_2") (pintype "input"))
      (node (ref "IC2") (pin "1") (pinfunction "Q_1") (pintype "bidirectional"))
      (node (ref "R2L") (pin "1") (pinfunction "1_1") (pintype "passive"))
    )
    (net (code "12") (name "/KEY3") (class "Default")
      (node (ref "IC14") (pin "2") (pinfunction "I1_2") (pintype "input"))
      (node (ref "IC3") (pin "1") (pinfunction "Q_1") (pintype "bidirectional"))
      (node (ref "R3L") (pin "1") (pinfunction "1_1") (pintype "passive"))
    )
    (net (code "13") (name "/KEY4") (class "Default")
      (node (ref "IC4") (pin "1") (pinfunction "Q_1") (pintype "bidirectional"))
      (node (ref "R4L") (pin "1") (pinfunction "1_1") (pintype "passive"))
      (node (ref "Z7") (pin "1") (pinfunction "1_1") (pintype "passive"))
    )
    (net (code "14") (name "/KEY5") (class "Default")
      (node (ref "IC5") (pin "1") (pinfunction "Q_1") (pintype "bidirectional"))
      (node (ref "R5L") (pin "1") (pinfunction "1_1") (pintype "passive"))
      (node (ref "Z8") (pin "1") (pinfunction "1_1") (pintype "passive"))
    )
    (net (code "15") (name "/KEY6") (class "Default")
      (node (ref "IC13") (pin "5") (pinfunction "I1_5") (pintype "input"))
      (node (ref "IC6") (pin "1") (pinfunction "Q_1") (pintype "bidirectional"))
      (node (ref "R6L") (pin "1") (pinfunction "1_1") (pintype "passive"))
    )
    (net (code "16") (name "/KEY7") (class "Default")
      (node (ref "IC14") (pin "5") (pinfunction "I1_5") (pintype "input"))
      (node (ref "IC7") (pin "1") (pinfunction "Q_1") (pintype "bidirectional"))
      (node (ref "R7L") (pin "1") (pinfunction "1_1") (pintype "passive"))
    )
    (net (code "17") (name "/KEY8") (class "Default")
      (node (ref "IC8") (pin "1") (pinfunction "Q_1") (pintype "bidirectional"))
      (node (ref "R8L") (pin "1") (pinfunction "1_1") (pintype "passive"))
      (node (ref "Z6") (pin "1") (pinfunction "1_1") (pintype "passive"))
    )
    (net (code "18") (name "555_CLK") (class "Default")
      (node (ref "IC19") (pin "3") (pinfunction "Q_3") (pintype "output"))
      (node (ref "U$22") (pin "P$2") (pinfunction "2_P$2") (pintype "passive"))
    )
    (net (code "19") (name "555_VCC") (class "Default")
      (node (ref "C20") (pin "1") (pinfunction "1_1") (pintype "passive"))
      (node (ref "IC19") (pin "4") (pinfunction "R_4") (pintype "input"))
      (node (ref "IC19") (pin "8") (pinfunction "V+_8") (pintype "power_in"))
      (node (ref "U$5") (pin "P$2") (pinfunction "2_P$2") (pintype "bidirectional"))
      (node (ref "Z9") (pin "1") (pinfunction "1_1") (pintype "passive"))
    )
    (net (code "20") (name "CLK_SUM") (class "Default")
      (node (ref "IC15") (pin "14") (pinfunction "CLK_14") (pintype "input"))
      (node (ref "IC16") (pin "6") (pinfunction "O_6") (pintype "output"))
      (node (ref "R10Q") (pin "1") (pinfunction "1_1") (pintype "passive"))
    )
    (net (code "21") (name "GND") (class "Default")
      (node (ref "C1") (pin "2") (pinfunction "2_2") (pintype "passive"))
      (node (ref "C10") (pin "2") (pinfunction "2_2") (pintype "passive"))
      (node (ref "C10S") (pin "2") (pinfunction "2_2") (pintype "passive"))
      (node (ref "C11") (pin "2") (pinfunction "2_2") (pintype "passive"))
      (node (ref "C11S") (pin "2") (pinfunction "2_2") (pintype "passive"))
      (node (ref "C12") (pin "2") (pinfunction "2_2") (pintype "passive"))
      (node (ref "C12S") (pin "2") (pinfunction "2_2") (pintype "passive"))
      (node (ref "C1P") (pin "-") (pinfunction "-_-") (pintype "passive"))
      (node (ref "C1S") (pin "2") (pinfunction "2_2") (pintype "passive"))
      (node (ref "C2") (pin "2") (pinfunction "2_2") (pintype "passive"))
      (node (ref "C20") (pin "2") (pinfunction "2_2") (pintype "passive"))
      (node (ref "C2P") (pin "2") (pinfunction "2_2") (pintype "passive"))
      (node (ref "C2S") (pin "2") (pinfunction "2_2") (pintype "passive"))
      (node (ref "C3") (pin "2") (pinfunction "2_2") (pintype "passive"))
      (node (ref "C3P") (pin "2") (pinfunction "2_2") (pintype "passive"))
      (node (ref "C3S") (pin "2") (pinfunction "2_2") (pintype "passive"))
      (node (ref "C4") (pin "2") (pinfunction "2_2") (pintype "passive"))
      (node (ref "C4S") (pin "2") (pinfunction "2_2") (pintype "passive"))
      (node (ref "C5") (pin "2") (pinfunction "2_2") (pintype "passive"))
      (node (ref "C5S") (pin "2") (pinfunction "2_2") (pintype "passive"))
      (node (ref "C6") (pin "2") (pinfunction "2_2") (pintype "passive"))
      (node (ref "C6S") (pin "2") (pinfunction "2_2") (pintype "passive"))
      (node (ref "C7") (pin "2") (pinfunction "2_2") (pintype "passive"))
      (node (ref "C7S") (pin "2") (pinfunction "2_2") (pintype "passive"))
      (node (ref "C8") (pin "2") (pinfunction "2_2") (pintype "passive"))
      (node (ref "C8S") (pin "2") (pinfunction "2_2") (pintype "passive"))
      (node (ref "C9") (pin "2") (pinfunction "2_2") (pintype "passive"))
      (node (ref "C9S") (pin "2") (pinfunction "2_2") (pintype "passive"))
      (node (ref "D1P") (pin "A") (pinfunction "A_A") (pintype "passive"))
      (node (ref "DSA") (pin "-") (pinfunction "-_-") (pintype "passive"))
      (node (ref "IC1") (pin "2") (pinfunction "VSS_2") (pintype "bidirectional"))
      (node (ref "IC1") (pin "4") (pinfunction "AHLB_4") (pintype "bidirectional"))
      (node (ref "IC10") (pin "2") (pinfunction "VSS_2") (pintype "bidirectional"))
      (node (ref "IC10") (pin "4") (pinfunction "AHLB_4") (pintype "bidirectional"))
      (node (ref "IC10") (pin "6") (pinfunction "TOG_6") (pintype "bidirectional"))
      (node (ref "IC11") (pin "2") (pinfunction "VSS_2") (pintype "bidirectional"))
      (node (ref "IC11") (pin "4") (pinfunction "AHLB_4") (pintype "bidirectional"))
      (node (ref "IC12") (pin "2") (pinfunction "VSS_2") (pintype "bidirectional"))
      (node (ref "IC12") (pin "4") (pinfunction "AHLB_4") (pintype "bidirectional"))
      (node (ref "IC13") (pin "7") (pinfunction "GND_7") (pintype "power_in"))
      (node (ref "IC14") (pin "7") (pinfunction "GND_7") (pintype "power_in"))
      (node (ref "IC15") (pin "13") (pinfunction "ENA_13") (pintype "input"))
      (node (ref "IC15") (pin "8") (pinfunction "VSS_8") (pintype "power_in"))
      (node (ref "IC18") (pin "10") (pinfunction "VS_10") (pintype "power_in"))
      (node (ref "IC19") (pin "1") (pinfunction "GND_1") (pintype "power_in"))
      (node (ref "IC2") (pin "2") (pinfunction "VSS_2") (pintype "bidirectional"))
      (node (ref "IC2") (pin "4") (pinfunction "AHLB_4") (pintype "bidirectional"))
      (node (ref "IC20") (pin "1") (pinfunction "GND_1") (pintype "power_in"))
      (node (ref "IC3") (pin "2") (pinfunction "VSS_2") (pintype "bidirectional"))
      (node (ref "IC3") (pin "4") (pinfunction "AHLB_4") (pintype "bidirectional"))
      (node (ref "IC4") (pin "2") (pinfunction "VSS_2") (pintype "bidirectional"))
      (node (ref "IC4") (pin "4") (pinfunction "AHLB_4") (pintype "bidirectional"))
      (node (ref "IC5") (pin "2") (pinfunction "VSS_2") (pintype "bidirectional"))
      (node (ref "IC5") (pin "4") (pinfunction "AHLB_4") (pintype "bidirectional"))
      (node (ref "IC6") (pin "2") (pinfunction "VSS_2") (pintype "bidirectional"))
      (node (ref "IC6") (pin "4") (pinfunction "AHLB_4") (pintype "bidirectional"))
      (node (ref "IC7") (pin "2") (pinfunction "VSS_2") (pintype "bidirectional"))
      (node (ref "IC7") (pin "4") (pinfunction "AHLB_4") (pintype "bidirectional"))
      (node (ref "IC8") (pin "2") (pinfunction "VSS_2") (pintype "bidirectional"))
      (node (ref "IC8") (pin "4") (pinfunction "AHLB_4") (pintype "bidirectional"))
      (node (ref "IC9") (pin "2") (pinfunction "VSS_2") (pintype "bidirectional"))
      (node (ref "IC9") (pin "4") (pinfunction "AHLB_4") (pintype "bidirectional"))
      (node (ref "IC9") (pin "6") (pinfunction "TOG_6") (pintype "bidirectional"))
      (node (ref "LED1") (pin "P$1") (pinfunction "C_P$1") (pintype "passive"))
      (node (ref "LED10") (pin "P$1") (pinfunction "C_P$1") (pintype "passive"))
      (node (ref "LED11") (pin "P$1") (pinfunction "C_P$1") (pintype "passive"))
      (node (ref "LED12") (pin "P$1") (pinfunction "C_P$1") (pintype "passive"))
      (node (ref "LED2") (pin "P$1") (pinfunction "C_P$1") (pintype "passive"))
      (node (ref "LED3") (pin "P$1") (pinfunction "C_P$1") (pintype "passive"))
      (node (ref "LED4") (pin "P$1") (pinfunction "C_P$1") (pintype "passive"))
      (node (ref "LED5") (pin "P$1") (pinfunction "C_P$1") (pintype "passive"))
      (node (ref "LED6") (pin "P$1") (pinfunction "C_P$1") (pintype "passive"))
      (node (ref "LED7") (pin "P$1") (pinfunction "C_P$1") (pintype "passive"))
      (node (ref "LED8") (pin "P$1") (pinfunction "C_P$1") (pintype "passive"))
      (node (ref "LED9") (pin "P$1") (pinfunction "C_P$1") (pintype "passive"))
      (node (ref "POWER") (pin "3") (pinfunction "3_3") (pintype "passive"))
      (node (ref "POWER") (pin "4") (pinfunction "4_4") (pintype "passive"))
      (node (ref "POWER") (pin "5") (pinfunction "5_5") (pintype "passive"))
      (node (ref "POWER") (pin "6") (pinfunction "6_6") (pintype "passive"))
      (node (ref "POWER") (pin "7") (pinfunction "7_7") (pintype "passive"))
      (node (ref "POWER") (pin "8") (pinfunction "8_8") (pintype "passive"))
      (node (ref "R3Q1") (pin "1") (pinfunction "1_1") (pintype "passive"))
      (node (ref "R3Q1") (pin "2") (pinfunction "2_2") (pintype "passive"))
      (node (ref "U$1") (pin "P$9") (pinfunction "9_P$9") (pintype "passive"))
      (node (ref "U$22") (pin "P$6") (pinfunction "6_P$6") (pintype "passive"))
    )
    (net (code "22") (name "INT{slash}EXT_CLK") (class "Default")
      (node (ref "IC17") (pin "4") (pinfunction "I0_4") (pintype "input"))
      (node (ref "U$22") (pin "P$4") (pinfunction "4_P$4") (pintype "passive"))
    )
    (net (code "23") (name "INT{slash}EXT_RST") (class "Default")
      (node (ref "IC17") (pin "1") (pinfunction "I0_1") (pintype "input"))
      (node (ref "U$22") (pin "P$3") (pinfunction "3_P$3") (pintype "passive"))
    )
    (net (code "24") (name "MAN_CLK") (class "Default")
      (node (ref "IC10") (pin "1") (pinfunction "Q_1") (pintype "bidirectional"))
      (node (ref "IC16") (pin "4") (pinfunction "I0_4") (pintype "input"))
      (node (ref "R10L") (pin "2") (pinfunction "2_2") (pintype "passive"))
    )
    (net (code "25") (name "MAN_RST") (class "Default")
      (node (ref "IC16") (pin "1") (pinfunction "I0_1") (pintype "input"))
      (node (ref "IC9") (pin "1") (pinfunction "Q_1") (pintype "bidirectional"))
      (node (ref "R9L") (pin "2") (pinfunction "2_2") (pintype "passive"))
    )
    (net (code "26") (name "Net-(D1P-PadC)") (class "Default")
      (node (ref "D1P") (pin "C") (pinfunction "C_C") (pintype "passive"))
      (node (ref "F1") (pin "1") (pinfunction "1_1") (pintype "passive"))
      (node (ref "POWER") (pin "10") (pinfunction "10_10") (pintype "passive"))
      (node (ref "POWER") (pin "9") (pinfunction "9_9") (pintype "passive"))
    )
    (net (code "27") (name "Net-(IC1-I)") (class "Default")
      (node (ref "C1S") (pin "1") (pinfunction "1_1") (pintype "passive"))
      (node (ref "IC1") (pin "3") (pinfunction "I_3") (pintype "bidirectional"))
      (node (ref "TP1") (pin "P$1") (pinfunction "2_P$1") (pintype "passive"))
    )
    (net (code "28") (name "Net-(IC2-I)") (class "Default")
      (node (ref "C2S") (pin "1") (pinfunction "1_1") (pintype "passive"))
      (node (ref "IC2") (pin "3") (pinfunction "I_3") (pintype "bidirectional"))
      (node (ref "TP2") (pin "P$1") (pinfunction "2_P$1") (pintype "passive"))
    )
    (net (code "29") (name "Net-(IC3-I)") (class "Default")
      (node (ref "C3S") (pin "1") (pinfunction "1_1") (pintype "passive"))
      (node (ref "IC3") (pin "3") (pinfunction "I_3") (pintype "bidirectional"))
      (node (ref "TP3") (pin "P$1") (pinfunction "2_P$1") (pintype "passive"))
    )
    (net (code "30") (name "Net-(IC4-I)") (class "Default")
      (node (ref "C4S") (pin "1") (pinfunction "1_1") (pintype "passive"))
      (node (ref "IC4") (pin "3") (pinfunction "I_3") (pintype "bidirectional"))
      (node (ref "TP4") (pin "P$1") (pinfunction "2_P$1") (pintype "passive"))
    )
    (net (code "31") (name "Net-(IC5-I)") (class "Default")
      (node (ref "C5S") (pin "1") (pinfunction "1_1") (pintype "passive"))
      (node (ref "IC5") (pin "3") (pinfunction "I_3") (pintype "bidirectional"))
      (node (ref "TP5") (pin "P$1") (pinfunction "2_P$1") (pintype "passive"))
    )
    (net (code "32") (name "Net-(IC5-TOG)") (class "Default")
      (node (ref "C5") (pin "1") (pinfunction "1_1") (pintype "passive"))
      (node (ref "IC5") (pin "5") (pinfunction "VDD_5") (pintype "bidirectional"))
      (node (ref "IC5") (pin "6") (pinfunction "TOG_6") (pintype "bidirectional"))
      (node (ref "Z1") (pin "1") (pinfunction "1_1") (pintype "passive"))
    )
    (net (code "33") (name "Net-(IC6-I)") (class "Default")
      (node (ref "C6S") (pin "1") (pinfunction "1_1") (pintype "passive"))
      (node (ref "IC6") (pin "3") (pinfunction "I_3") (pintype "bidirectional"))
      (node (ref "TP6") (pin "P$1") (pinfunction "2_P$1") (pintype "passive"))
    )
    (net (code "34") (name "Net-(IC6-TOG)") (class "Default")
      (node (ref "C6") (pin "1") (pinfunction "1_1") (pintype "passive"))
      (node (ref "IC6") (pin "5") (pinfunction "VDD_5") (pintype "bidirectional"))
      (node (ref "IC6") (pin "6") (pinfunction "TOG_6") (pintype "bidirectional"))
      (node (ref "Z2") (pin "1") (pinfunction "1_1") (pintype "passive"))
    )
    (net (code "35") (name "Net-(IC7-I)") (class "Default")
      (node (ref "C7S") (pin "1") (pinfunction "1_1") (pintype "passive"))
      (node (ref "IC7") (pin "3") (pinfunction "I_3") (pintype "bidirectional"))
      (node (ref "TP7") (pin "P$1") (pinfunction "2_P$1") (pintype "passive"))
    )
    (net (code "36") (name "Net-(IC7-TOG)") (class "Default")
      (node (ref "C7") (pin "1") (pinfunction "1_1") (pintype "passive"))
      (node (ref "IC7") (pin "5") (pinfunction "VDD_5") (pintype "bidirectional"))
      (node (ref "IC7") (pin "6") (pinfunction "TOG_6") (pintype "bidirectional"))
      (node (ref "Z3") (pin "1") (pinfunction "1_1") (pintype "passive"))
    )
    (net (code "37") (name "Net-(IC8-I)") (class "Default")
      (node (ref "C8S") (pin "1") (pinfunction "1_1") (pintype "passive"))
      (node (ref "IC8") (pin "3") (pinfunction "I_3") (pintype "bidirectional"))
      (node (ref "TP8") (pin "P$1") (pinfunction "2_P$1") (pintype "passive"))
    )
    (net (code "38") (name "Net-(IC9-I)") (class "Default")
      (node (ref "C9S") (pin "1") (pinfunction "1_1") (pintype "passive"))
      (node (ref "IC9") (pin "3") (pinfunction "I_3") (pintype "bidirectional"))
      (node (ref "TP13") (pin "P$1") (pinfunction "2_P$1") (pintype "passive"))
    )
    (net (code "39") (name "Net-(IC10-I)") (class "Default")
      (node (ref "C10S") (pin "1") (pinfunction "1_1") (pintype "passive"))
      (node (ref "IC10") (pin "3") (pinfunction "I_3") (pintype "bidirectional"))
      (node (ref "TP11") (pin "P$1") (pinfunction "2_P$1") (pintype "passive"))
    )
    (net (code "40") (name "Net-(IC11-I)") (class "Default")
      (node (ref "C11S") (pin "1") (pinfunction "1_1") (pintype "passive"))
      (node (ref "IC11") (pin "3") (pinfunction "I_3") (pintype "bidirectional"))
      (node (ref "TP12") (pin "P$1") (pinfunction "2_P$1") (pintype "passive"))
    )
    (net (code "41") (name "Net-(IC11-Q)") (class "Default")
      (node (ref "IC11") (pin "1") (pinfunction "Q_1") (pintype "bidirectional"))
      (node (ref "IC17") (pin "5") (pinfunction "I1_5") (pintype "input"))
      (node (ref "R11L") (pin "2") (pinfunction "2_2") (pintype "passive"))
    )
    (net (code "42") (name "Net-(IC12-I)") (class "Default")
      (node (ref "C12S") (pin "1") (pinfunction "1_1") (pintype "passive"))
      (node (ref "IC12") (pin "3") (pinfunction "I_3") (pintype "bidirectional"))
      (node (ref "TP10") (pin "P$1") (pinfunction "2_P$1") (pintype "passive"))
    )
    (net (code "43") (name "Net-(IC12-Q)") (class "Default")
      (node (ref "IC12") (pin "1") (pinfunction "Q_1") (pintype "bidirectional"))
      (node (ref "R12L") (pin "2") (pinfunction "2_2") (pintype "passive"))
      (node (ref "Z10") (pin "1") (pinfunction "1_1") (pintype "passive"))
    )
    (net (code "44") (name "Net-(IC13A-O)") (class "Default")
      (node (ref "IC13") (pin "3") (pinfunction "O_3") (pintype "output"))
      (node (ref "U$8") (pin "P$1") (pinfunction "2_P$1") (pintype "passive"))
    )
    (net (code "45") (name "Net-(IC13B-O)") (class "Default")
      (node (ref "IC13") (pin "6") (pinfunction "O_6") (pintype "output"))
      (node (ref "U$12") (pin "P$1") (pinfunction "2_P$1") (pintype "passive"))
    )
    (net (code "46") (name "Net-(IC13C-I1)") (class "Default")
      (node (ref "IC13") (pin "10") (pinfunction "I1_10") (pintype "input"))
      (node (ref "Z8") (pin "2") (pinfunction "2_2") (pintype "passive"))
    )
    (net (code "47") (name "Net-(IC13C-O)") (class "Default")
      (node (ref "IC13") (pin "8") (pinfunction "O_8") (pintype "output"))
      (node (ref "U$11") (pin "P$1") (pinfunction "2_P$1") (pintype "passive"))
    )
    (net (code "48") (name "Net-(IC13D-O)") (class "Default")
      (node (ref "IC13") (pin "11") (pinfunction "O_11") (pintype "output"))
      (node (ref "U$7") (pin "P$1") (pinfunction "2_P$1") (pintype "passive"))
    )
    (net (code "49") (name "Net-(IC14A-O)") (class "Default")
      (node (ref "IC14") (pin "3") (pinfunction "O_3") (pintype "output"))
      (node (ref "U$9") (pin "P$1") (pinfunction "2_P$1") (pintype "passive"))
    )
    (net (code "50") (name "Net-(IC14B-O)") (class "Default")
      (node (ref "IC14") (pin "6") (pinfunction "O_6") (pintype "output"))
      (node (ref "U$13") (pin "P$1") (pinfunction "2_P$1") (pintype "passive"))
    )
    (net (code "51") (name "Net-(IC14C-I0)") (class "Default")
      (node (ref "IC14") (pin "9") (pinfunction "I0_9") (pintype "input"))
      (node (ref "Z4") (pin "2") (pinfunction "2_2") (pintype "passive"))
    )
    (net (code "52") (name "Net-(IC14C-I1)") (class "Default")
      (node (ref "IC14") (pin "10") (pinfunction "I1_10") (pintype "input"))
      (node (ref "Z6") (pin "2") (pinfunction "2_2") (pintype "passive"))
    )
    (net (code "53") (name "Net-(IC14C-O)") (class "Default")
      (node (ref "IC14") (pin "8") (pinfunction "O_8") (pintype "output"))
      (node (ref "U$14") (pin "P$1") (pinfunction "2_P$1") (pintype "passive"))
    )
    (net (code "54") (name "Net-(IC14D-I0)") (class "Default")
      (node (ref "IC14") (pin "12") (pinfunction "I0_12") (pintype "input"))
      (node (ref "Z5") (pin "2") (pinfunction "2_2") (pintype "passive"))
    )
    (net (code "55") (name "Net-(IC14D-I1)") (class "Default")
      (node (ref "IC14") (pin "13") (pinfunction "I1_13") (pintype "input"))
      (node (ref "Z7") (pin "2") (pinfunction "2_2") (pintype "passive"))
    )
    (net (code "56") (name "Net-(IC14D-O)") (class "Default")
      (node (ref "IC14") (pin "11") (pinfunction "O_11") (pintype "output"))
      (node (ref "U$10") (pin "P$1") (pinfunction "2_P$1") (pintype "passive"))
    )
    (net (code "57") (name "Net-(IC16A-I1)") (class "Default")
      (node (ref "IC16") (pin "2") (pinfunction "I1_2") (pintype "input"))
      (node (ref "U$23") (pin "P$1") (pinfunction "2_P$1") (pintype "passive"))
    )
    (net (code "58") (name "Net-(IC16B-I1)") (class "Default")
      (node (ref "IC16") (pin "5") (pinfunction "I1_5") (pintype "input"))
      (node (ref "U$26") (pin "P$1") (pinfunction "2_P$1") (pintype "passive"))
    )
    (net (code "59") (name "Net-(IC17A-I1)") (class "Default")
      (node (ref "IC17") (pin "2") (pinfunction "I1_2") (pintype "input"))
      (node (ref "Z10") (pin "2") (pinfunction "2_2") (pintype "passive"))
    )
    (net (code "60") (name "Net-(IC17A-O)") (class "Default")
      (node (ref "IC17") (pin "3") (pinfunction "O_3") (pintype "output"))
      (node (ref "U$24") (pin "P$1") (pinfunction "2_P$1") (pintype "passive"))
    )
    (net (code "61") (name "Net-(IC17B-O)") (class "Default")
      (node (ref "IC17") (pin "6") (pinfunction "O_6") (pintype "output"))
      (node (ref "U$25") (pin "P$1") (pinfunction "2_P$1") (pintype "passive"))
    )
    (net (code "62") (name "Net-(IC18-IN1)") (class "Default")
      (node (ref "IC18") (pin "1") (pinfunction "IN1_1") (pintype "input"))
      (node (ref "U$2") (pin "P$1") (pinfunction "2_P$1") (pintype "passive"))
    )
    (net (code "63") (name "Net-(IC18-IN2)") (class "Default")
      (node (ref "IC18") (pin "2") (pinfunction "IN2_2") (pintype "input"))
      (node (ref "U$15") (pin "P$1") (pinfunction "2_P$1") (pintype "passive"))
    )
    (net (code "64") (name "Net-(IC18-IN3)") (class "Default")
      (node (ref "IC18") (pin "3") (pinfunction "IN3_3") (pintype "input"))
      (node (ref "U$16") (pin "P$1") (pinfunction "2_P$1") (pintype "passive"))
    )
    (net (code "65") (name "Net-(IC18-IN4)") (class "Default")
      (node (ref "IC18") (pin "4") (pinfunction "IN4_4") (pintype "input"))
      (node (ref "U$17") (pin "P$1") (pinfunction "2_P$1") (pintype "passive"))
    )
    (net (code "66") (name "Net-(IC18-IN5)") (class "Default")
      (node (ref "IC18") (pin "5") (pinfunction "IN5_5") (pintype "input"))
      (node (ref "U$18") (pin "P$1") (pinfunction "2_P$1") (pintype "passive"))
    )
    (net (code "67") (name "Net-(IC18-IN6)") (class "Default")
      (node (ref "IC18") (pin "6") (pinfunction "IN6_6") (pintype "input"))
      (node (ref "U$19") (pin "P$1") (pinfunction "2_P$1") (pintype "passive"))
    )
    (net (code "68") (name "Net-(IC18-IN7)") (class "Default")
      (node (ref "IC18") (pin "7") (pinfunction "IN7_7") (pintype "input"))
      (node (ref "U$20") (pin "P$1") (pinfunction "2_P$1") (pintype "passive"))
    )
    (net (code "69") (name "Net-(IC18-IN8)") (class "Default")
      (node (ref "IC18") (pin "8") (pinfunction "IN8_8") (pintype "input"))
      (node (ref "U$21") (pin "P$1") (pinfunction "2_P$1") (pintype "passive"))
    )
    (net (code "70") (name "Net-(IC18-OUT1)") (class "Default")
      (node (ref "IC18") (pin "18") (pinfunction "OUT1_18") (pintype "output"))
      (node (ref "U$1") (pin "P$1") (pinfunction "1_P$1") (pintype "passive"))
    )
    (net (code "71") (name "Net-(IC18-OUT2)") (class "Default")
      (node (ref "IC18") (pin "17") (pinfunction "OUT2_17") (pintype "output"))
      (node (ref "U$1") (pin "P$2") (pinfunction "2_P$2") (pintype "passive"))
    )
    (net (code "72") (name "Net-(IC18-OUT3)") (class "Default")
      (node (ref "IC18") (pin "16") (pinfunction "OUT3_16") (pintype "output"))
      (node (ref "U$1") (pin "P$3") (pinfunction "3_P$3") (pintype "passive"))
    )
    (net (code "73") (name "Net-(IC18-OUT4)") (class "Default")
      (node (ref "IC18") (pin "15") (pinfunction "OUT4_15") (pintype "output"))
      (node (ref "U$1") (pin "P$4") (pinfunction "4_P$4") (pintype "passive"))
    )
    (net (code "74") (name "Net-(IC18-OUT5)") (class "Default")
      (node (ref "IC18") (pin "14") (pinfunction "OUT5_14") (pintype "output"))
      (node (ref "U$1") (pin "P$5") (pinfunction "5_P$5") (pintype "passive"))
    )
    (net (code "75") (name "Net-(IC18-OUT6)") (class "Default")
      (node (ref "IC18") (pin "13") (pinfunction "OUT6_13") (pintype "output"))
      (node (ref "U$1") (pin "P$6") (pinfunction "6_P$6") (pintype "passive"))
    )
    (net (code "76") (name "Net-(IC18-OUT7)") (class "Default")
      (node (ref "IC18") (pin "12") (pinfunction "OUT7_12") (pintype "output"))
      (node (ref "U$1") (pin "P$7") (pinfunction "7_P$7") (pintype "passive"))
    )
    (net (code "77") (name "Net-(IC18-OUT8)") (class "Default")
      (node (ref "IC18") (pin "11") (pinfunction "OUT8_11") (pintype "output"))
      (node (ref "U$1") (pin "P$8") (pinfunction "8_P$8") (pintype "passive"))
    )
    (net (code "78") (name "Net-(IC19-DIS)") (class "Default")
      (node (ref "IC19") (pin "7") (pinfunction "DIS_7") (pintype "input"))
      (node (ref "R1") (pin "2") (pinfunction "2_2") (pintype "passive"))
      (node (ref "U$5") (pin "P$1") (pinfunction "1_P$1") (pintype "bidirectional"))
    )
    (net (code "79") (name "Net-(IC19-THR)") (class "Default")
      (node (ref "DSA") (pin "+") (pinfunction "+_+") (pintype "passive"))
      (node (ref "IC19") (pin "2") (pinfunction "TR_2") (pintype "input"))
      (node (ref "IC19") (pin "6") (pinfunction "THR_6") (pintype "input"))
      (node (ref "R1") (pin "1") (pinfunction "1_1") (pintype "passive"))
    )
    (net (code "80") (name "Net-(IC20-VIN)") (class "Default")
      (node (ref "C1P") (pin "+") (pinfunction "+_+") (pintype "passive"))
      (node (ref "C2P") (pin "1") (pinfunction "1_1") (pintype "passive"))
      (node (ref "F1") (pin "2") (pinfunction "2_2") (pintype "passive"))
      (node (ref "IC20") (pin "3") (pinfunction "VIN_3") (pintype "input"))
    )
    (net (code "81") (name "Net-(LED1-AG)") (class "Default")
      (node (ref "LED1") (pin "P$3") (pinfunction "AG_P$3") (pintype "passive"))
      (node (ref "R1L") (pin "2") (pinfunction "2_2") (pintype "passive"))
    )
    (net (code "82") (name "Net-(LED1-AR)") (class "Default")
      (node (ref "LED1") (pin "P$2") (pinfunction "AR_P$2") (pintype "passive"))
      (node (ref "R1Q") (pin "2") (pinfunction "2_2") (pintype "passive"))
    )
    (net (code "83") (name "Net-(LED2-AG)") (class "Default")
      (node (ref "LED2") (pin "P$3") (pinfunction "AG_P$3") (pintype "passive"))
      (node (ref "R2L") (pin "2") (pinfunction "2_2") (pintype "passive"))
    )
    (net (code "84") (name "Net-(LED2-AR)") (class "Default")
      (node (ref "LED2") (pin "P$2") (pinfunction "AR_P$2") (pintype "passive"))
      (node (ref "R2Q") (pin "2") (pinfunction "2_2") (pintype "passive"))
    )
    (net (code "85") (name "Net-(LED3-AG)") (class "Default")
      (node (ref "LED3") (pin "P$3") (pinfunction "AG_P$3") (pintype "passive"))
      (node (ref "R3L") (pin "2") (pinfunction "2_2") (pintype "passive"))
    )
    (net (code "86") (name "Net-(LED3-AR)") (class "Default")
      (node (ref "LED3") (pin "P$2") (pinfunction "AR_P$2") (pintype "passive"))
      (node (ref "R3Q") (pin "2") (pinfunction "2_2") (pintype "passive"))
    )
    (net (code "87") (name "Net-(LED4-AG)") (class "Default")
      (node (ref "LED4") (pin "P$3") (pinfunction "AG_P$3") (pintype "passive"))
      (node (ref "R4L") (pin "2") (pinfunction "2_2") (pintype "passive"))
    )
    (net (code "88") (name "Net-(LED4-AR)") (class "Default")
      (node (ref "LED4") (pin "P$2") (pinfunction "AR_P$2") (pintype "passive"))
      (node (ref "R4Q") (pin "2") (pinfunction "2_2") (pintype "passive"))
    )
    (net (code "89") (name "Net-(LED5-AG)") (class "Default")
      (node (ref "LED5") (pin "P$3") (pinfunction "AG_P$3") (pintype "passive"))
      (node (ref "R5L") (pin "2") (pinfunction "2_2") (pintype "passive"))
    )
    (net (code "90") (name "Net-(LED5-AR)") (class "Default")
      (node (ref "LED5") (pin "P$2") (pinfunction "AR_P$2") (pintype "passive"))
      (node (ref "R5Q") (pin "2") (pinfunction "2_2") (pintype "passive"))
    )
    (net (code "91") (name "Net-(LED6-AG)") (class "Default")
      (node (ref "LED6") (pin "P$3") (pinfunction "AG_P$3") (pintype "passive"))
      (node (ref "R6L") (pin "2") (pinfunction "2_2") (pintype "passive"))
    )
    (net (code "92") (name "Net-(LED6-AR)") (class "Default")
      (node (ref "LED6") (pin "P$2") (pinfunction "AR_P$2") (pintype "passive"))
      (node (ref "R6Q") (pin "1") (pinfunction "1_1") (pintype "passive"))
    )
    (net (code "93") (name "Net-(LED7-AG)") (class "Default")
      (node (ref "LED7") (pin "P$3") (pinfunction "AG_P$3") (pintype "passive"))
      (node (ref "R7L") (pin "2") (pinfunction "2_2") (pintype "passive"))
    )
    (net (code "94") (name "Net-(LED7-AR)") (class "Default")
      (node (ref "LED7") (pin "P$2") (pinfunction "AR_P$2") (pintype "passive"))
      (node (ref "R7Q") (pin "1") (pinfunction "1_1") (pintype "passive"))
    )
    (net (code "95") (name "Net-(LED8-AG)") (class "Default")
      (node (ref "LED8") (pin "P$3") (pinfunction "AG_P$3") (pintype "passive"))
      (node (ref "R8L") (pin "2") (pinfunction "2_2") (pintype "passive"))
    )
    (net (code "96") (name "Net-(LED8-AR)") (class "Default")
      (node (ref "LED8") (pin "P$2") (pinfunction "AR_P$2") (pintype "passive"))
      (node (ref "R8Q") (pin "2") (pinfunction "2_2") (pintype "passive"))
    )
    (net (code "97") (name "Net-(LED9-AG)") (class "Default")
      (node (ref "LED9") (pin "P$3") (pinfunction "AG_P$3") (pintype "passive"))
      (node (ref "R10Q") (pin "2") (pinfunction "2_2") (pintype "passive"))
    )
    (net (code "98") (name "Net-(LED9-AR)") (class "Default")
      (node (ref "LED9") (pin "P$2") (pinfunction "AR_P$2") (pintype "passive"))
      (node (ref "R10L") (pin "1") (pinfunction "1_1") (pintype "passive"))
    )
    (net (code "99") (name "Net-(LED10-AG)") (class "Default")
      (node (ref "LED10") (pin "P$3") (pinfunction "AG_P$3") (pintype "passive"))
      (node (ref "R9Q") (pin "1") (pinfunction "1_1") (pintype "passive"))
    )
    (net (code "100") (name "Net-(LED10-AR)") (class "Default")
      (node (ref "LED10") (pin "P$2") (pinfunction "AR_P$2") (pintype "passive"))
      (node (ref "R9L") (pin "1") (pinfunction "1_1") (pintype "passive"))
    )
    (net (code "101") (name "Net-(LED11-AR)") (class "Default")
      (node (ref "LED11") (pin "P$2") (pinfunction "AR_P$2") (pintype "passive"))
      (node (ref "R12L") (pin "1") (pinfunction "1_1") (pintype "passive"))
    )
    (net (code "102") (name "Net-(LED12-AR)") (class "Default")
      (node (ref "LED12") (pin "P$2") (pinfunction "AR_P$2") (pintype "passive"))
      (node (ref "R11L") (pin "1") (pinfunction "1_1") (pintype "passive"))
    )
    (net (code "103") (name "RST_SEL") (class "Default")
      (node (ref "U$22") (pin "P$1") (pinfunction "1_P$1") (pintype "passive"))
      (node (ref "U$4") (pin "P$1") (pinfunction "1_P$1") (pintype "passive"))
    )
    (net (code "104") (name "RST_SUM") (class "Default")
      (node (ref "IC15") (pin "15") (pinfunction "RES_15") (pintype "input"))
      (node (ref "IC16") (pin "3") (pinfunction "O_3") (pintype "output"))
      (node (ref "R9Q") (pin "2") (pinfunction "2_2") (pintype "passive"))
    )
    (net (code "105") (name "VCC") (class "Default")
      (node (ref "C1") (pin "1") (pinfunction "1_1") (pintype "passive"))
      (node (ref "C10") (pin "1") (pinfunction "1_1") (pintype "passive"))
      (node (ref "C11") (pin "1") (pinfunction "1_1") (pintype "passive"))
      (node (ref "C12") (pin "1") (pinfunction "1_1") (pintype "passive"))
      (node (ref "C2") (pin "1") (pinfunction "1_1") (pintype "passive"))
      (node (ref "C3") (pin "1") (pinfunction "1_1") (pintype "passive"))
      (node (ref "C3P") (pin "1") (pinfunction "1_1") (pintype "passive"))
      (node (ref "C4") (pin "1") (pinfunction "1_1") (pintype "passive"))
      (node (ref "C8") (pin "1") (pinfunction "1_1") (pintype "passive"))
      (node (ref "C9") (pin "1") (pinfunction "1_1") (pintype "passive"))
      (node (ref "IC1") (pin "5") (pinfunction "VDD_5") (pintype "bidirectional"))
      (node (ref "IC1") (pin "6") (pinfunction "TOG_6") (pintype "bidirectional"))
      (node (ref "IC10") (pin "5") (pinfunction "VDD_5") (pintype "bidirectional"))
      (node (ref "IC11") (pin "5") (pinfunction "VDD_5") (pintype "bidirectional"))
      (node (ref "IC11") (pin "6") (pinfunction "TOG_6") (pintype "bidirectional"))
      (node (ref "IC12") (pin "5") (pinfunction "VDD_5") (pintype "bidirectional"))
      (node (ref "IC12") (pin "6") (pinfunction "TOG_6") (pintype "bidirectional"))
      (node (ref "IC13") (pin "14") (pinfunction "VCC_14") (pintype "power_in"))
      (node (ref "IC14") (pin "14") (pinfunction "VCC_14") (pintype "power_in"))
      (node (ref "IC15") (pin "16") (pinfunction "VDD_16") (pintype "power_in"))
      (node (ref "IC18") (pin "9") (pinfunction "GND_9") (pintype "power_in"))
      (node (ref "IC2") (pin "5") (pinfunction "VDD_5") (pintype "bidirectional"))
      (node (ref "IC2") (pin "6") (pinfunction "TOG_6") (pintype "bidirectional"))
      (node (ref "IC20") (pin "2") (pinfunction "VOUT_2") (pintype "output"))
      (node (ref "IC3") (pin "5") (pinfunction "VDD_5") (pintype "bidirectional"))
      (node (ref "IC3") (pin "6") (pinfunction "TOG_6") (pintype "bidirectional"))
      (node (ref "IC4") (pin "5") (pinfunction "VDD_5") (pintype "bidirectional"))
      (node (ref "IC4") (pin "6") (pinfunction "TOG_6") (pintype "bidirectional"))
      (node (ref "IC8") (pin "5") (pinfunction "VDD_5") (pintype "bidirectional"))
      (node (ref "IC8") (pin "6") (pinfunction "TOG_6") (pintype "bidirectional"))
      (node (ref "IC9") (pin "5") (pinfunction "VDD_5") (pintype "bidirectional"))
      (node (ref "Z1") (pin "2") (pinfunction "2_2") (pintype "passive"))
      (node (ref "Z2") (pin "2") (pinfunction "2_2") (pintype "passive"))
      (node (ref "Z3") (pin "2") (pinfunction "2_2") (pintype "passive"))
      (node (ref "Z9") (pin "2") (pinfunction "2_2") (pintype "passive"))
    )
    (net (code "106") (name "unconnected-(IC15A-CO-Pad12)") (class "Default")
      (node (ref "IC15") (pin "12") (pinfunction "CO_12") (pintype "output"))
    )
    (net (code "107") (name "unconnected-(IC15A-Q9-Pad11)") (class "Default")
      (node (ref "IC15") (pin "11") (pinfunction "Q9_11") (pintype "output"))
    )
    (net (code "108") (name "unconnected-(IC19-CV-Pad5)") (class "Default")
      (node (ref "IC19") (pin "5") (pinfunction "CV_5") (pintype "input"))
    )
    (net (code "109") (name "unconnected-(LED11-AG-PadP$3)") (class "Default")
      (node (ref "LED11") (pin "P$3") (pinfunction "AG_P$3") (pintype "passive"))
    )
    (net (code "110") (name "unconnected-(LED12-AG-PadP$3)") (class "Default")
      (node (ref "LED12") (pin "P$3") (pinfunction "AG_P$3") (pintype "passive"))
    )
    (net (code "111") (name "unconnected-(POWER-Pad1)") (class "Default")
      (node (ref "POWER") (pin "1") (pinfunction "1_1") (pintype "passive"))
    )
    (net (code "112") (name "unconnected-(POWER-Pad2)") (class "Default")
      (node (ref "POWER") (pin "2") (pinfunction "2_2") (pintype "passive"))
    )
    (net (code "113") (name "unconnected-(U$1-10-PadP$10)") (class "Default")
      (node (ref "U$1") (pin "P$10") (pinfunction "10_P$10") (pintype "passive"))
    )
    (net (code "114") (name "unconnected-(U$22-5-PadP$5)") (class "Default")
      (node (ref "U$22") (pin "P$5") (pinfunction "5_P$5") (pintype "passive"))
    )
  )
)
